# DA15.net
KiCad netlist of a schematic drawn in EasyEDA Pro
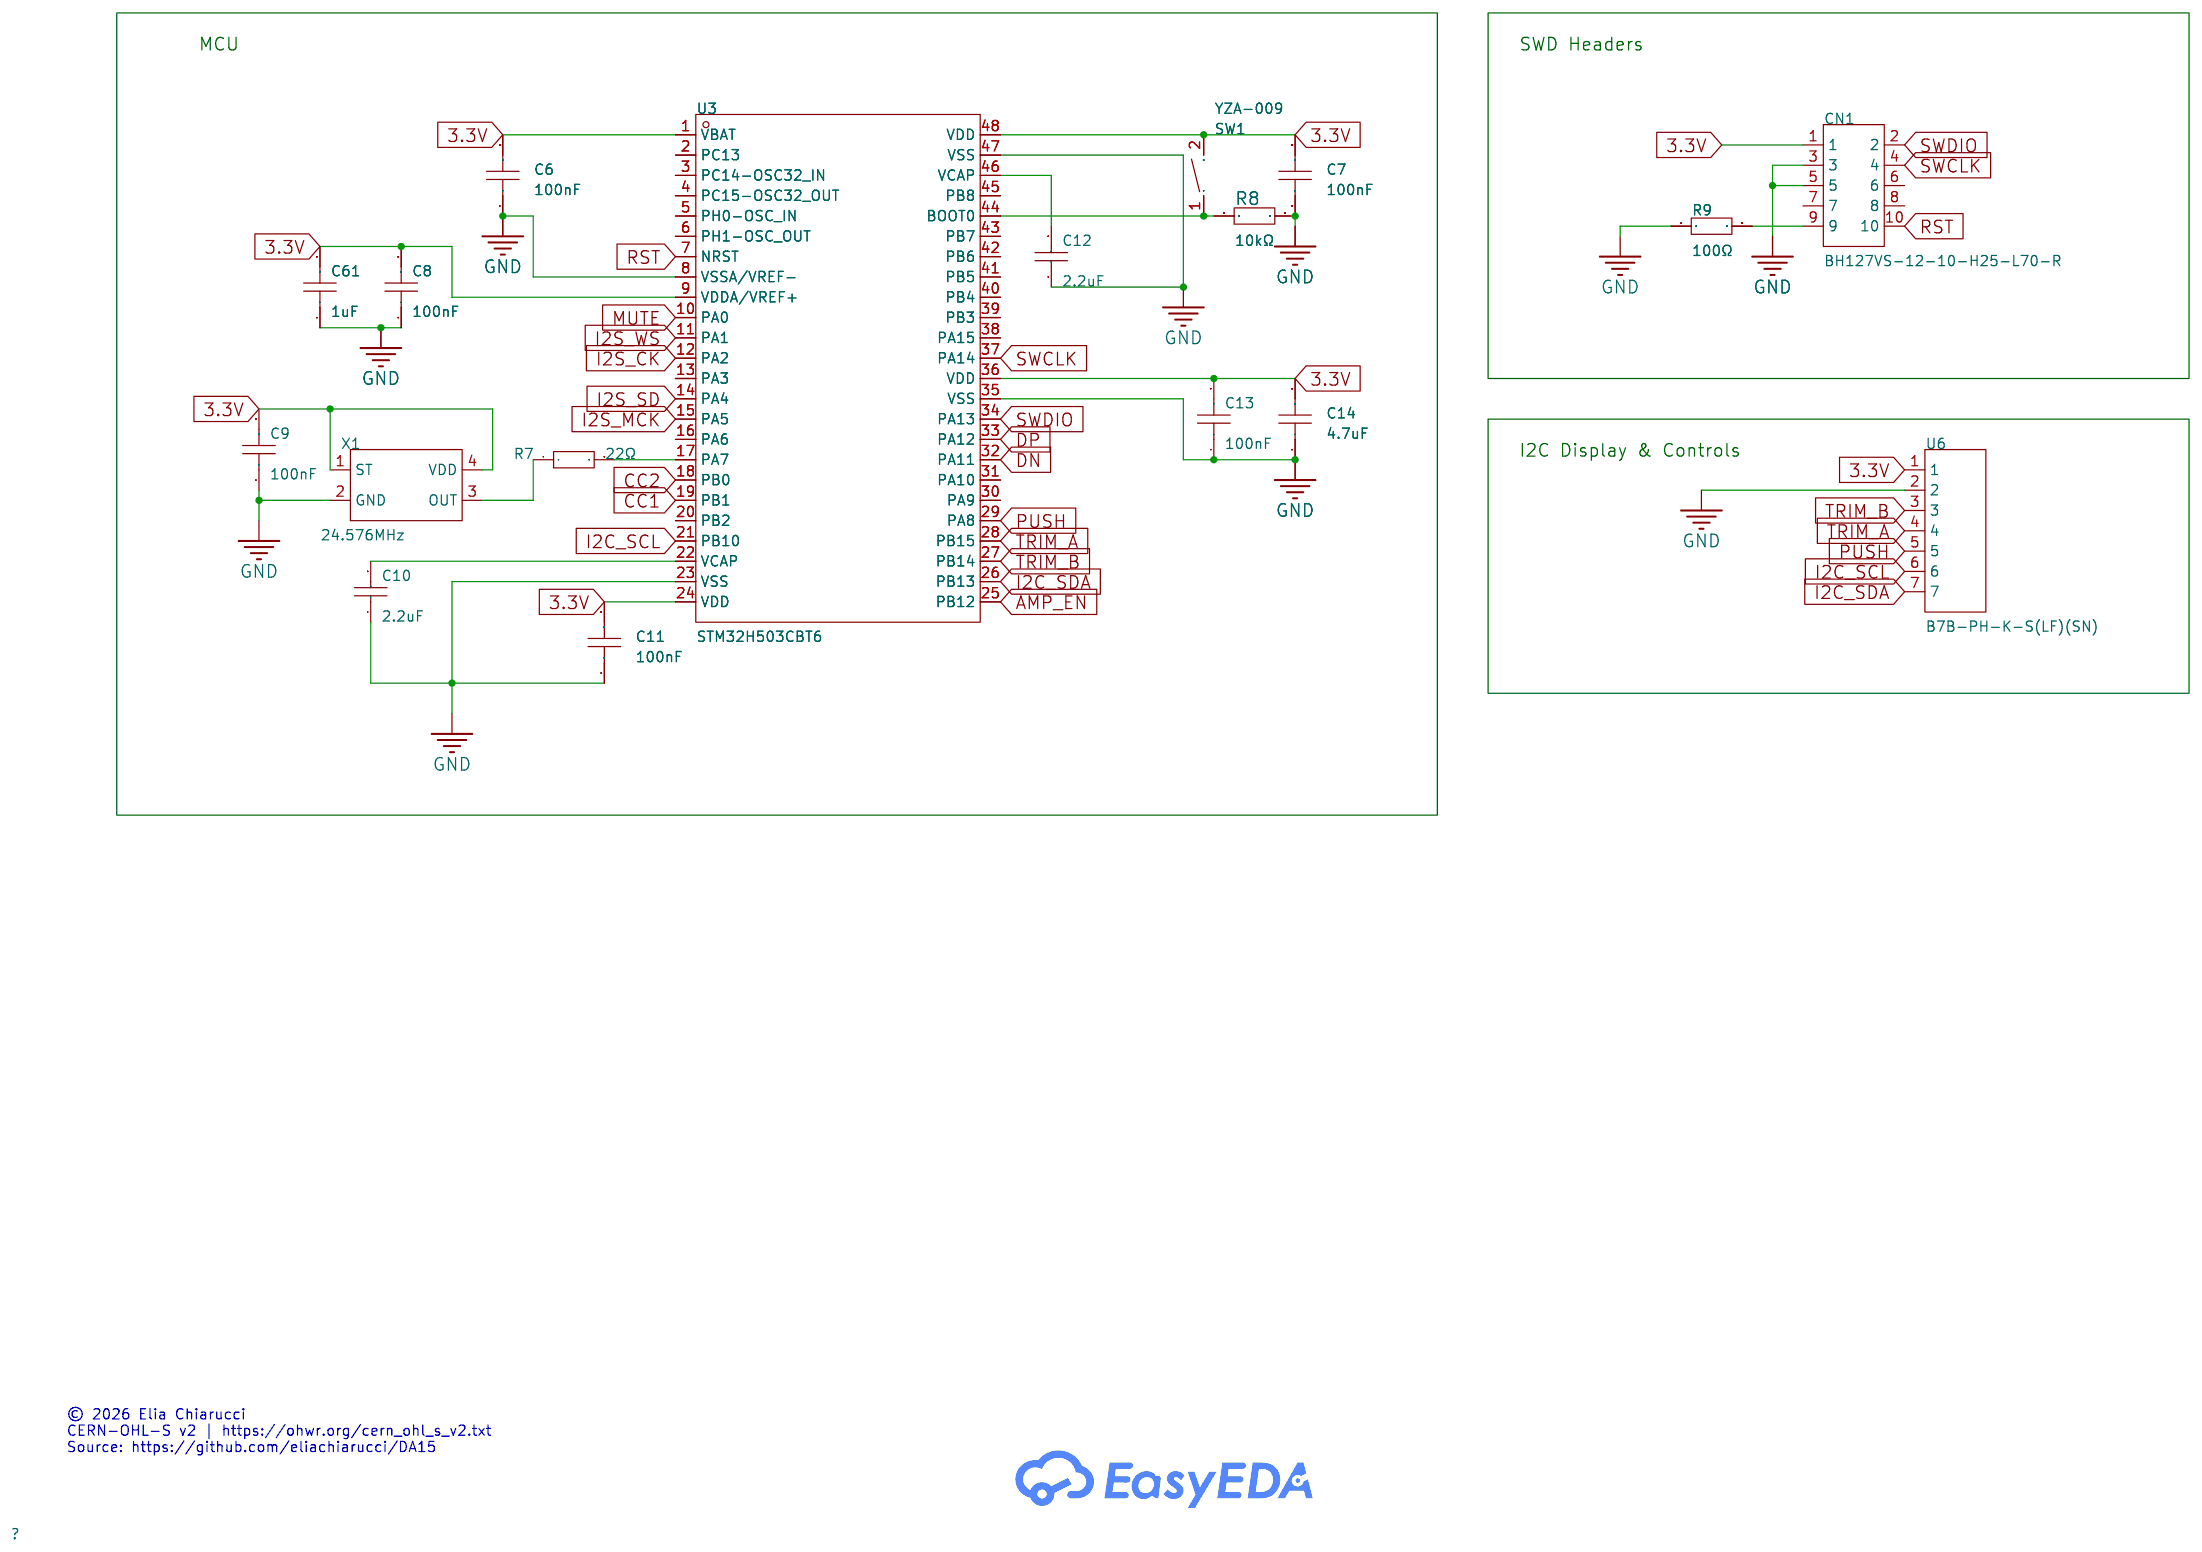
[diagram p0: Controller]
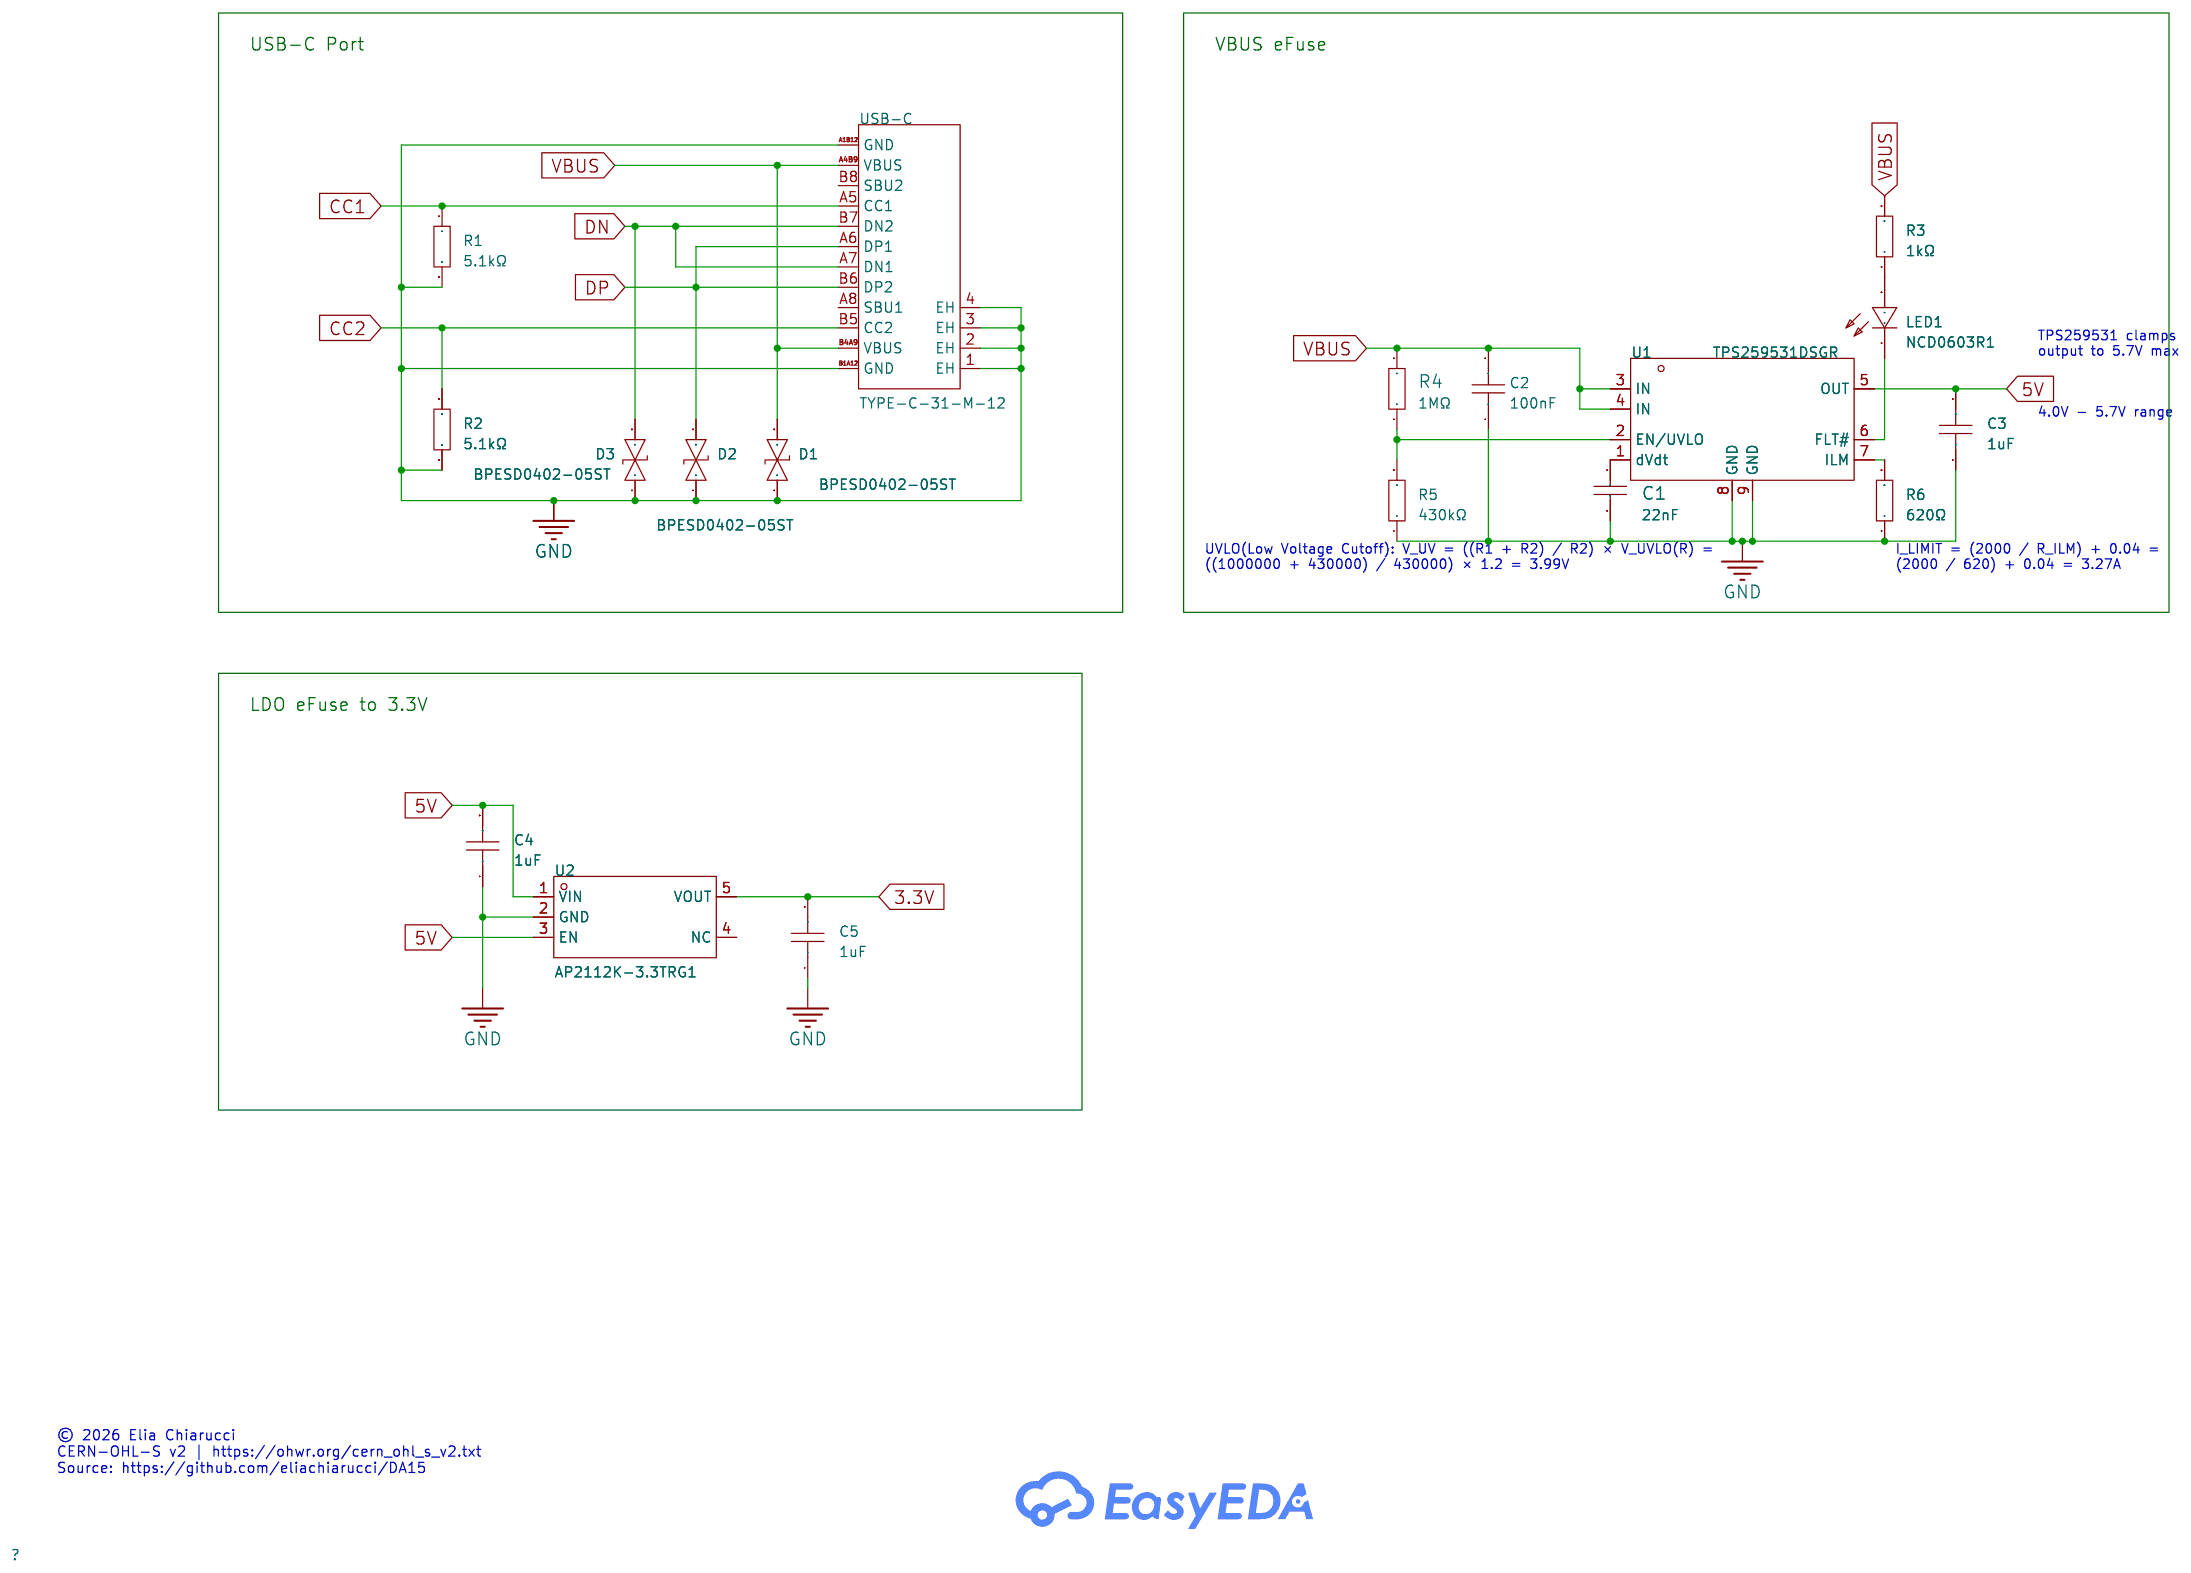
[diagram p1: Power]
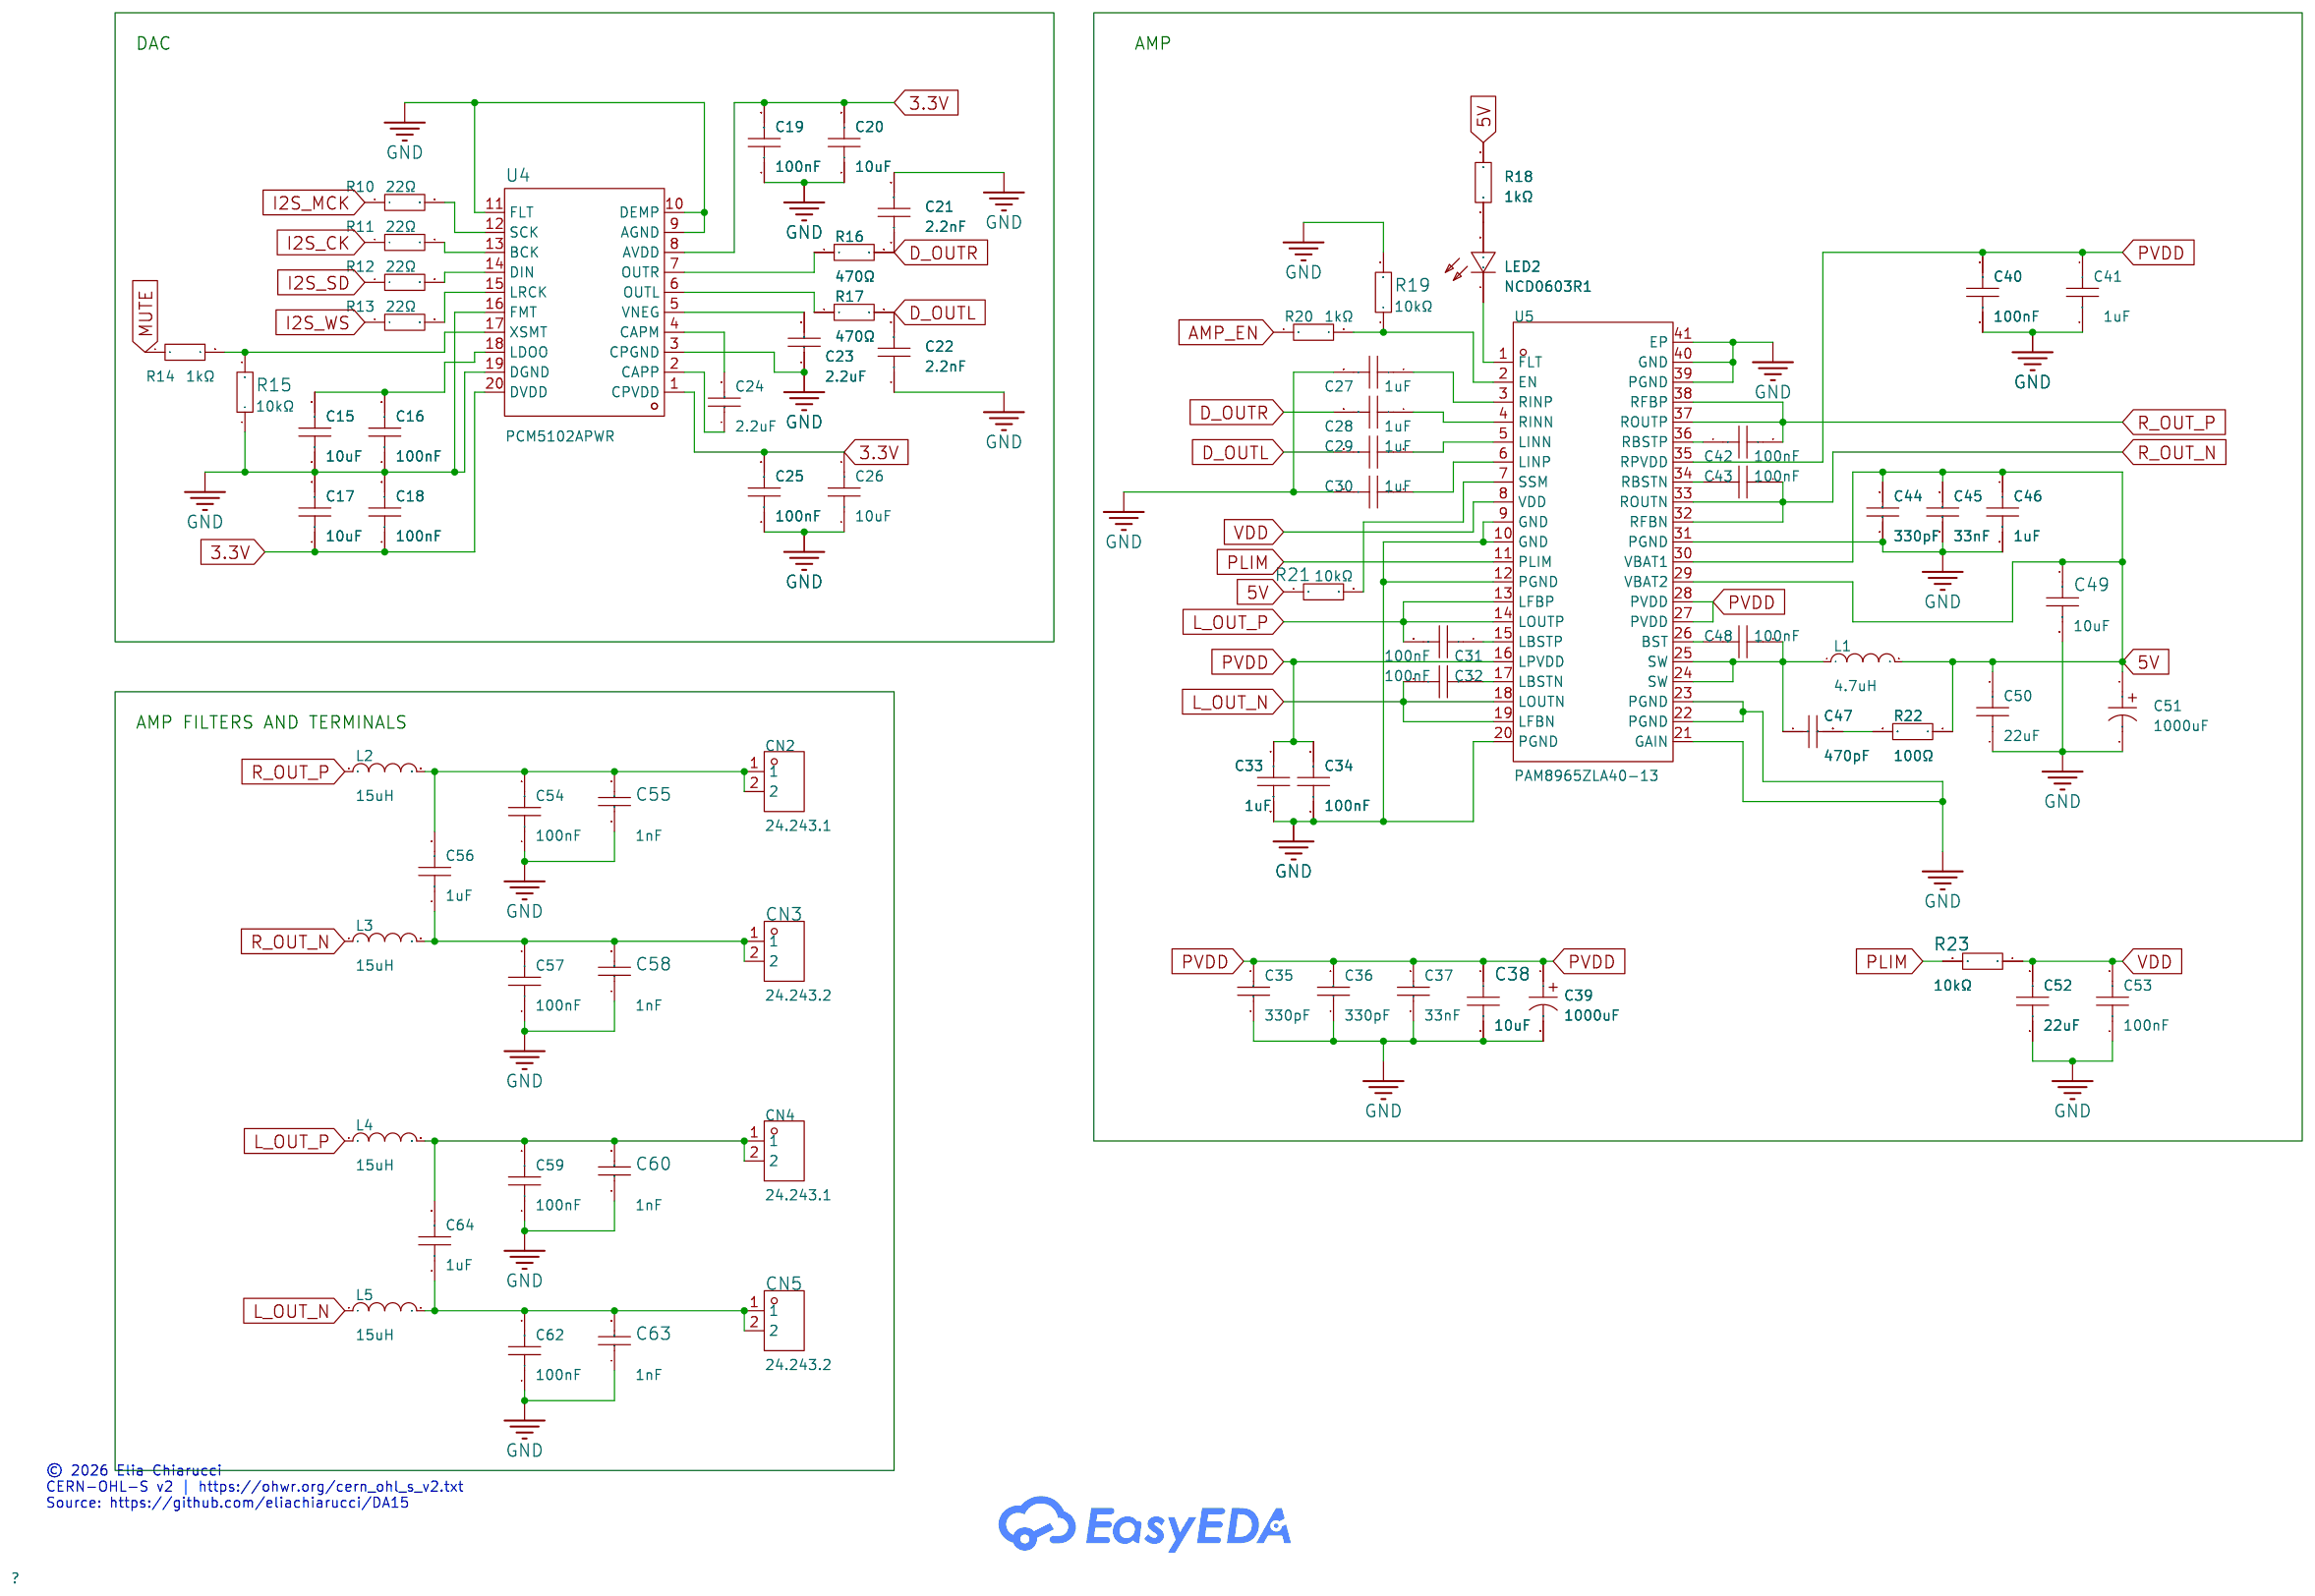
[diagram p2: Audio]

(export (version "E")
  (design (tool "Eeschema 10.0.6"))
  (components
    (comp (ref "C6")
      (value "100nF")
      (footprint "easyedapro:C0603")
      (description "Capacitance:100nF Tolerance:±10% Tolerance:±10% Voltage Rating:50V Temperature Coefficient:X7R")
      (fields
        (field (name "Manufacturer Part") "CC0603KRX7R9BB104")
        (field (name "Manufacturer") "YAGEO(国巨)")
      )
      (libsource (lib "easyedapro") (part "CC0603KRX7R9BB104"))
    )
    (comp (ref "C7")
      (value "100nF")
      (footprint "easyedapro:C0603")
      (description "Capacitance:100nF Tolerance:±10% Tolerance:±10% Voltage Rating:50V Temperature Coefficient:X7R")
      (fields
        (field (name "Manufacturer Part") "CC0603KRX7R9BB104")
        (field (name "Manufacturer") "YAGEO(国巨)")
      )
      (libsource (lib "easyedapro") (part "CC0603KRX7R9BB104"))
    )
    (comp (ref "C8")
      (value "100nF")
      (footprint "easyedapro:C0603")
      (description "Capacitance:100nF Tolerance:±10% Tolerance:±10% Voltage Rating:50V Temperature Coefficient:X7R")
      (fields
        (field (name "Manufacturer Part") "CC0603KRX7R9BB104")
        (field (name "Manufacturer") "YAGEO(国巨)")
      )
      (libsource (lib "easyedapro") (part "CC0603KRX7R9BB104"))
    )
    (comp (ref "C9")
      (value "100nF")
      (footprint "easyedapro:C0603")
      (description "Capacitance:100nF Tolerance:±10% Tolerance:±10% Voltage Rating:50V Temperature Coefficient:X7R")
      (fields
        (field (name "Manufacturer Part") "CC0603KRX7R9BB104")
        (field (name "Manufacturer") "YAGEO(国巨)")
      )
      (libsource (lib "easyedapro") (part "CC0603KRX7R9BB104"))
    )
    (comp (ref "C10")
      (value "2.2uF")
      (footprint "easyedapro:C0603")
      (description "Capacitance:2.2uF Tolerance:±10% Tolerance:±10% Voltage Rating:16V Temperature Coefficient:X5R")
      (fields
        (field (name "Manufacturer Part") "CL10A225KO8NNNC")
        (field (name "Manufacturer") "SAMSUNG(三星)")
      )
      (libsource (lib "easyedapro") (part "CL10A225KO8NNNC"))
    )
    (comp (ref "C11")
      (value "100nF")
      (footprint "easyedapro:C0603")
      (description "Capacitance:100nF Tolerance:±10% Tolerance:±10% Voltage Rating:50V Temperature Coefficient:X7R")
      (fields
        (field (name "Manufacturer Part") "CC0603KRX7R9BB104")
        (field (name "Manufacturer") "YAGEO(国巨)")
      )
      (libsource (lib "easyedapro") (part "CC0603KRX7R9BB104"))
    )
    (comp (ref "C12")
      (value "2.2uF")
      (footprint "easyedapro:C0603")
      (description "Capacitance:2.2uF Tolerance:±10% Tolerance:±10% Voltage Rating:16V Temperature Coefficient:X5R")
      (fields
        (field (name "Manufacturer Part") "CL10A225KO8NNNC")
        (field (name "Manufacturer") "SAMSUNG(三星)")
      )
      (libsource (lib "easyedapro") (part "CL10A225KO8NNNC"))
    )
    (comp (ref "C13")
      (value "100nF")
      (footprint "easyedapro:C0603")
      (description "Capacitance:100nF Tolerance:±10% Tolerance:±10% Voltage Rating:50V Temperature Coefficient:X7R")
      (fields
        (field (name "Manufacturer Part") "CC0603KRX7R9BB104")
        (field (name "Manufacturer") "YAGEO(国巨)")
      )
      (libsource (lib "easyedapro") (part "CC0603KRX7R9BB104"))
    )
    (comp (ref "C14")
      (value "4.7uF")
      (footprint "easyedapro:C0603")
      (description "Capacitance:4.7uF Tolerance:±10% Tolerance:±10% Voltage Rating:16V Temperature Coefficient:X5R")
      (fields
        (field (name "Manufacturer Part") "CL10A475KO8NNNC")
        (field (name "Manufacturer") "SAMSUNG(三星)")
      )
      (libsource (lib "easyedapro") (part "CL10A475KO8NNNC"))
    )
    (comp (ref "C61")
      (value "1uF")
      (footprint "easyedapro:C0603")
      (description "Capacitance:1uF Tolerance:±10% Tolerance:±10% Voltage Rating:50V Temperature Coefficient:X5R")
      (fields
        (field (name "Manufacturer Part") "CL10A105KB8NNNC")
        (field (name "Manufacturer") "SAMSUNG(三星)")
      )
      (libsource (lib "easyedapro") (part "CL10A105KB8NNNC"))
    )
    (comp (ref "CN1")
      (value "BH127VS-12-10-H25-L70-R")
      (footprint "easyedapro:CONN-SMD_10P-P1.27-V-M-R2-C5-LS5.8_BH127VS-12-10-H25-L70-R")
      (fields (field (name "Manufacturer") "XFCN(兴飞)"))
      (libsource (lib "easyedapro") (part "BH127VS-12-10-H25-L70-R"))
    )
    (comp (ref "R7")
      (value "22Ω")
      (footprint "easyedapro:R0603")
      (fields
        (field (name "Manufacturer Part") "0603WAF220JT5E")
        (field (name "Manufacturer") "UNI-ROYAL(厚声)")
      )
      (libsource (lib "easyedapro") (part "0603WAF220JT5E"))
    )
    (comp (ref "R8")
      (value "10kΩ")
      (footprint "easyedapro:R0603")
      (fields
        (field (name "Manufacturer Part") "0603WAF1002T5E")
        (field (name "Manufacturer") "UNI-ROYAL(厚声)")
      )
      (libsource (lib "easyedapro") (part "0603WAF1002T5E"))
    )
    (comp (ref "R9")
      (value "100Ω")
      (footprint "easyedapro:R0603")
      (fields
        (field (name "Manufacturer Part") "0603WAF1000T5E")
        (field (name "Manufacturer") "UNI-ROYAL(厚声)")
      )
      (libsource (lib "easyedapro") (part "0603WAF1000T5E"))
    )
    (comp (ref "SW1")
      (value "YZA-009")
      (footprint "easyedapro:SW-SMD_YZA-009")
      (fields (field (name "Manufacturer") "YIZHI(逸致)"))
      (libsource (lib "easyedapro") (part "YZA-009"))
    )
    (comp (ref "U3")
      (value "STM32H503CBT6")
      (footprint "easyedapro:LQFP-48_L7.0-W7.0-P0.50-LS9.0-BL")
      (fields (field (name "Manufacturer") "ST(意法半导体)"))
      (libsource (lib "easyedapro") (part "STM32H503CBT6"))
    )
    (comp (ref "U6")
      (value "B7B-PH-K-S(LF)(SN)")
      (footprint "easyedapro:CONN-TH_B7B-PH-K-S-LF-SN")
      (fields (field (name "Manufacturer") "JST"))
      (libsource (lib "easyedapro") (part "B7B-PH-K-S-(LF)(SN)"))
    )
    (comp (ref "X1")
      (value "24.576MHz")
      (footprint "easyedapro:OSC-SMD_4P-L2.5-W2.0-BL")
      (fields
        (field (name "Manufacturer Part") "OT3EL4C4JI-111OLP-24.576M")
        (field (name "Manufacturer") "YXC(扬兴晶振)")
      )
      (libsource (lib "easyedapro") (part "OT3EL4C4JI-111OLP-24.576M"))
    )
    (comp (ref "C1")
      (value "22nF")
      (footprint "easyedapro:C0603")
      (description "Capacitance:22nF Tolerance:±10% Tolerance:±10% Voltage Rating:50V Temperature Coefficient:X7R")
      (fields
        (field (name "Manufacturer Part") "CL10B223KB8NNNC")
        (field (name "Manufacturer") "SAMSUNG(三星)")
      )
      (libsource (lib "easyedapro") (part "CL10B223KB8NNNC"))
    )
    (comp (ref "C2")
      (value "100nF")
      (footprint "easyedapro:C0603")
      (description "Capacitance:100nF Tolerance:±10% Tolerance:±10% Voltage Rating:50V Temperature Coefficient:X7R")
      (fields
        (field (name "Manufacturer Part") "CC0603KRX7R9BB104")
        (field (name "Manufacturer") "YAGEO(国巨)")
      )
      (libsource (lib "easyedapro") (part "CC0603KRX7R9BB104"))
    )
    (comp (ref "C3")
      (value "1uF")
      (footprint "easyedapro:C0603")
      (description "Capacitance:1uF Tolerance:±10% Tolerance:±10% Voltage Rating:50V Temperature Coefficient:X5R")
      (fields
        (field (name "Manufacturer Part") "CL10A105KB8NNNC")
        (field (name "Manufacturer") "SAMSUNG(三星)")
      )
      (libsource (lib "easyedapro") (part "CL10A105KB8NNNC"))
    )
    (comp (ref "C4")
      (value "1uF")
      (footprint "easyedapro:C0603")
      (description "Capacitance:1uF Tolerance:±10% Tolerance:±10% Voltage Rating:50V Temperature Coefficient:X5R")
      (fields
        (field (name "Manufacturer Part") "CL10A105KB8NNNC")
        (field (name "Manufacturer") "SAMSUNG(三星)")
      )
      (libsource (lib "easyedapro") (part "CL10A105KB8NNNC"))
    )
    (comp (ref "C5")
      (value "1uF")
      (footprint "easyedapro:C0603")
      (description "Capacitance:1uF Tolerance:±10% Tolerance:±10% Voltage Rating:50V Temperature Coefficient:X5R")
      (fields
        (field (name "Manufacturer Part") "CL10A105KB8NNNC")
        (field (name "Manufacturer") "SAMSUNG(三星)")
      )
      (libsource (lib "easyedapro") (part "CL10A105KB8NNNC"))
    )
    (comp (ref "D1")
      (value "BPESD0402-05ST")
      (footprint "easyedapro:D0402-BI")
      (fields (field (name "Manufacturer") "BORN(伯恩半导体)"))
      (libsource (lib "easyedapro") (part "BPESD0402-05ST"))
    )
    (comp (ref "D2")
      (value "BPESD0402-05ST")
      (footprint "easyedapro:D0402-BI")
      (fields (field (name "Manufacturer") "BORN(伯恩半导体)"))
      (libsource (lib "easyedapro") (part "BPESD0402-05ST"))
    )
    (comp (ref "D3")
      (value "BPESD0402-05ST")
      (footprint "easyedapro:D0402-BI")
      (fields (field (name "Manufacturer") "BORN(伯恩半导体)"))
      (libsource (lib "easyedapro") (part "BPESD0402-05ST"))
    )
    (comp (ref "LED1")
      (value "NCD0603R1")
      (footprint "easyedapro:LED0603-RD_RED")
      (fields (field (name "Manufacturer") "国星光电"))
      (libsource (lib "easyedapro") (part "FC-DA1608HRK-620D"))
    )
    (comp (ref "R1")
      (value "5.1kΩ")
      (footprint "easyedapro:R0603")
      (fields
        (field (name "Manufacturer Part") "0603WAF5101T5E")
        (field (name "Manufacturer") "UNI-ROYAL(厚声)")
      )
      (libsource (lib "easyedapro") (part "0603WAF5101T5E"))
    )
    (comp (ref "R2")
      (value "5.1kΩ")
      (footprint "easyedapro:R0603")
      (fields
        (field (name "Manufacturer Part") "0603WAF5101T5E")
        (field (name "Manufacturer") "UNI-ROYAL(厚声)")
      )
      (libsource (lib "easyedapro") (part "0603WAF5101T5E"))
    )
    (comp (ref "R3")
      (value "1kΩ")
      (footprint "easyedapro:R0603")
      (fields
        (field (name "Manufacturer Part") "0603WAF1001T5E")
        (field (name "Manufacturer") "UNI-ROYAL(厚声)")
      )
      (libsource (lib "easyedapro") (part "0603WAF1001T5E"))
    )
    (comp (ref "R4")
      (value "1MΩ")
      (footprint "easyedapro:R0603")
      (fields
        (field (name "Manufacturer Part") "0603WAF1004T5E")
        (field (name "Manufacturer") "UNI-ROYAL(厚声)")
      )
      (libsource (lib "easyedapro") (part "0603WAF1004T5E"))
    )
    (comp (ref "R5")
      (value "430kΩ")
      (footprint "easyedapro:R0603")
      (fields
        (field (name "Manufacturer Part") "0603WAF4303T5E")
        (field (name "Manufacturer") "UNI-ROYAL(厚声)")
      )
      (libsource (lib "easyedapro") (part "0603WAF4303T5E"))
    )
    (comp (ref "R6")
      (value "620Ω")
      (footprint "easyedapro:R0603")
      (fields
        (field (name "Manufacturer Part") "0603WAF6200T5E")
        (field (name "Manufacturer") "UNI-ROYAL(厚声)")
      )
      (libsource (lib "easyedapro") (part "0603WAF6200T5E"))
    )
    (comp (ref "U1")
      (value "TPS259531DSGR")
      (footprint "easyedapro:WSON-8_L2.0-W2.0-P0.50-TL-EP")
      (fields (field (name "Manufacturer") "TI(德州仪器)"))
      (libsource (lib "easyedapro") (part "TPS259531DSGR"))
    )
    (comp (ref "U2")
      (value "AP2112K-3.3TRG1")
      (footprint "easyedapro:SOT-25-5_L2.9-W1.6-P0.95-LS2.8-BL")
      (fields (field (name "Manufacturer") "DIODES(美台)"))
      (libsource (lib "easyedapro") (part "AP2112K-3.3TRG1"))
    )
    (comp (ref "USB-C")
      (value "TYPE-C-31-M-12")
      (footprint "easyedapro:USB-C_SMD-TYPE-C-31-M-12_1")
      (fields (field (name "Manufacturer") "韩国韩荣"))
      (libsource (lib "easyedapro") (part "TYPE-C-31-M-12"))
    )
    (comp (ref "C15")
      (value "10uF")
      (footprint "easyedapro:C0603")
      (description "Capacitance:10uF Tolerance:±10% Tolerance:±10% Voltage Rating:10V Temperature Coefficient:X5R")
      (fields
        (field (name "Manufacturer Part") "CL10A106KP8NNNC")
        (field (name "Manufacturer") "SAMSUNG(三星)")
      )
      (libsource (lib "easyedapro") (part "CL10A106KP8NNNC"))
    )
    (comp (ref "C16")
      (value "100nF")
      (footprint "easyedapro:C0603")
      (description "Capacitance:100nF Tolerance:±10% Tolerance:±10% Voltage Rating:50V Temperature Coefficient:X7R")
      (fields
        (field (name "Manufacturer Part") "CC0603KRX7R9BB104")
        (field (name "Manufacturer") "YAGEO(国巨)")
      )
      (libsource (lib "easyedapro") (part "CC0603KRX7R9BB104"))
    )
    (comp (ref "C17")
      (value "10uF")
      (footprint "easyedapro:C0603")
      (description "Capacitance:10uF Tolerance:±10% Tolerance:±10% Voltage Rating:10V Temperature Coefficient:X5R")
      (fields
        (field (name "Manufacturer Part") "CL10A106KP8NNNC")
        (field (name "Manufacturer") "SAMSUNG(三星)")
      )
      (libsource (lib "easyedapro") (part "CL10A106KP8NNNC"))
    )
    (comp (ref "C18")
      (value "100nF")
      (footprint "easyedapro:C0603")
      (description "Capacitance:100nF Tolerance:±10% Tolerance:±10% Voltage Rating:50V Temperature Coefficient:X7R")
      (fields
        (field (name "Manufacturer Part") "CC0603KRX7R9BB104")
        (field (name "Manufacturer") "YAGEO(国巨)")
      )
      (libsource (lib "easyedapro") (part "CC0603KRX7R9BB104"))
    )
    (comp (ref "C19")
      (value "100nF")
      (footprint "easyedapro:C0603")
      (description "Capacitance:100nF Tolerance:±10% Tolerance:±10% Voltage Rating:50V Temperature Coefficient:X7R")
      (fields
        (field (name "Manufacturer Part") "CC0603KRX7R9BB104")
        (field (name "Manufacturer") "YAGEO(国巨)")
      )
      (libsource (lib "easyedapro") (part "CC0603KRX7R9BB104"))
    )
    (comp (ref "C20")
      (value "10uF")
      (footprint "easyedapro:C0603")
      (description "Capacitance:10uF Tolerance:±10% Tolerance:±10% Voltage Rating:10V Temperature Coefficient:X5R")
      (fields
        (field (name "Manufacturer Part") "CL10A106KP8NNNC")
        (field (name "Manufacturer") "SAMSUNG(三星)")
      )
      (libsource (lib "easyedapro") (part "CL10A106KP8NNNC"))
    )
    (comp (ref "C21")
      (value "2.2nF")
      (footprint "easyedapro:C0603")
      (fields
        (field (name "Manufacturer Part") "GCM1885C1H222FA16D")
        (field (name "Manufacturer") "muRata(村田)")
      )
      (libsource (lib "easyedapro") (part "GCM1885C1H222FA16D"))
    )
    (comp (ref "C22")
      (value "2.2nF")
      (footprint "easyedapro:C0603")
      (fields
        (field (name "Manufacturer Part") "GCM1885C1H222FA16D")
        (field (name "Manufacturer") "muRata(村田)")
      )
      (libsource (lib "easyedapro") (part "GCM1885C1H222FA16D"))
    )
    (comp (ref "C23")
      (value "2.2uF")
      (footprint "easyedapro:C0603")
      (description "Capacitance:2.2uF Tolerance:±10% Tolerance:±10% Voltage Rating:16V Temperature Coefficient:X5R")
      (fields
        (field (name "Manufacturer Part") "CL10A225KO8NNNC")
        (field (name "Manufacturer") "SAMSUNG(三星)")
      )
      (libsource (lib "easyedapro") (part "CL10A225KO8NNNC"))
    )
    (comp (ref "C24")
      (value "2.2uF")
      (footprint "easyedapro:C0603")
      (description "Capacitance:2.2uF Tolerance:±10% Tolerance:±10% Voltage Rating:16V Temperature Coefficient:X5R")
      (fields
        (field (name "Manufacturer Part") "CL10A225KO8NNNC")
        (field (name "Manufacturer") "SAMSUNG(三星)")
      )
      (libsource (lib "easyedapro") (part "CL10A225KO8NNNC"))
    )
    (comp (ref "C25")
      (value "100nF")
      (footprint "easyedapro:C0603")
      (description "Capacitance:100nF Tolerance:±10% Tolerance:±10% Voltage Rating:50V Temperature Coefficient:X7R")
      (fields
        (field (name "Manufacturer Part") "CC0603KRX7R9BB104")
        (field (name "Manufacturer") "YAGEO(国巨)")
      )
      (libsource (lib "easyedapro") (part "CC0603KRX7R9BB104"))
    )
    (comp (ref "C26")
      (value "10uF")
      (footprint "easyedapro:C0603")
      (description "Capacitance:10uF Tolerance:±10% Tolerance:±10% Voltage Rating:10V Temperature Coefficient:X5R")
      (fields
        (field (name "Manufacturer Part") "CL10A106KP8NNNC")
        (field (name "Manufacturer") "SAMSUNG(三星)")
      )
      (libsource (lib "easyedapro") (part "CL10A106KP8NNNC"))
    )
    (comp (ref "C27")
      (value "1uF")
      (footprint "easyedapro:C0603")
      (description "Capacitance:1uF Tolerance:±10% Tolerance:±10% Voltage Rating:50V Temperature Coefficient:X5R")
      (fields
        (field (name "Manufacturer Part") "CL10A105KB8NNNC")
        (field (name "Manufacturer") "SAMSUNG(三星)")
      )
      (libsource (lib "easyedapro") (part "CL10A105KB8NNNC"))
    )
    (comp (ref "C28")
      (value "1uF")
      (footprint "easyedapro:C0603")
      (description "Capacitance:1uF Tolerance:±10% Tolerance:±10% Voltage Rating:50V Temperature Coefficient:X5R")
      (fields
        (field (name "Manufacturer Part") "CL10A105KB8NNNC")
        (field (name "Manufacturer") "SAMSUNG(三星)")
      )
      (libsource (lib "easyedapro") (part "CL10A105KB8NNNC"))
    )
    (comp (ref "C29")
      (value "1uF")
      (footprint "easyedapro:C0603")
      (description "Capacitance:1uF Tolerance:±10% Tolerance:±10% Voltage Rating:50V Temperature Coefficient:X5R")
      (fields
        (field (name "Manufacturer Part") "CL10A105KB8NNNC")
        (field (name "Manufacturer") "SAMSUNG(三星)")
      )
      (libsource (lib "easyedapro") (part "CL10A105KB8NNNC"))
    )
    (comp (ref "C30")
      (value "1uF")
      (footprint "easyedapro:C0603")
      (description "Capacitance:1uF Tolerance:±10% Tolerance:±10% Voltage Rating:50V Temperature Coefficient:X5R")
      (fields
        (field (name "Manufacturer Part") "CL10A105KB8NNNC")
        (field (name "Manufacturer") "SAMSUNG(三星)")
      )
      (libsource (lib "easyedapro") (part "CL10A105KB8NNNC"))
    )
    (comp (ref "C31")
      (value "100nF")
      (footprint "easyedapro:C0603")
      (description "Capacitance:100nF Tolerance:±10% Tolerance:±10% Voltage Rating:50V Temperature Coefficient:X7R")
      (fields
        (field (name "Manufacturer Part") "CC0603KRX7R9BB104")
        (field (name "Manufacturer") "YAGEO(国巨)")
      )
      (libsource (lib "easyedapro") (part "CC0603KRX7R9BB104"))
    )
    (comp (ref "C32")
      (value "100nF")
      (footprint "easyedapro:C0603")
      (description "Capacitance:100nF Tolerance:±10% Tolerance:±10% Voltage Rating:50V Temperature Coefficient:X7R")
      (fields
        (field (name "Manufacturer Part") "CC0603KRX7R9BB104")
        (field (name "Manufacturer") "YAGEO(国巨)")
      )
      (libsource (lib "easyedapro") (part "CC0603KRX7R9BB104"))
    )
    (comp (ref "C33")
      (value "1uF")
      (footprint "easyedapro:C0603")
      (description "Capacitance:1uF Tolerance:±10% Tolerance:±10% Voltage Rating:50V Temperature Coefficient:X5R")
      (fields
        (field (name "Manufacturer Part") "CL10A105KB8NNNC")
        (field (name "Manufacturer") "SAMSUNG(三星)")
      )
      (libsource (lib "easyedapro") (part "CL10A105KB8NNNC"))
    )
    (comp (ref "C34")
      (value "100nF")
      (footprint "easyedapro:C0603")
      (description "Capacitance:100nF Tolerance:±10% Tolerance:±10% Voltage Rating:50V Temperature Coefficient:X7R")
      (fields
        (field (name "Manufacturer Part") "CC0603KRX7R9BB104")
        (field (name "Manufacturer") "YAGEO(国巨)")
      )
      (libsource (lib "easyedapro") (part "CC0603KRX7R9BB104"))
    )
    (comp (ref "C35")
      (value "330pF")
      (footprint "easyedapro:C0603")
      (description "Capacitance:330pF Tolerance:±5% Tolerance:±5% Voltage Rating:50V Temperature Coefficient:C0G")
      (fields
        (field (name "Manufacturer Part") "CL10C331JB8NNNC")
        (field (name "Manufacturer") "SAMSUNG(三星)")
      )
      (libsource (lib "easyedapro") (part "CL10C331JB8NNNC"))
    )
    (comp (ref "C36")
      (value "330pF")
      (footprint "easyedapro:C0603")
      (description "Capacitance:330pF Tolerance:±5% Tolerance:±5% Voltage Rating:50V Temperature Coefficient:C0G")
      (fields
        (field (name "Manufacturer Part") "CL10C331JB8NNNC")
        (field (name "Manufacturer") "SAMSUNG(三星)")
      )
      (libsource (lib "easyedapro") (part "CL10C331JB8NNNC"))
    )
    (comp (ref "C37")
      (value "33nF")
      (footprint "easyedapro:C0603")
      (description "Capacitance:33nF Tolerance:±10% Tolerance:±10% Voltage Rating:50V Temperature Coefficient:X7R")
      (fields
        (field (name "Manufacturer Part") "CL10B333KB8NNNC")
        (field (name "Manufacturer") "SAMSUNG(三星)")
      )
      (libsource (lib "easyedapro") (part "CL10B333KB8NNNC"))
    )
    (comp (ref "C38")
      (value "10uF")
      (footprint "easyedapro:C0603")
      (description "Capacitance:10uF Tolerance:±10% Tolerance:±10% Voltage Rating:25V Temperature Coefficient:X5R")
      (fields
        (field (name "Manufacturer Part") "GRM188R61E106KA73D")
        (field (name "Manufacturer") "muRata(村田)")
      )
      (libsource (lib "easyedapro") (part "GRM188R61E106KA73D"))
    )
    (comp (ref "C39")
      (value "1000uF")
      (footprint "easyedapro:CAP-TH_BD8.0-P3.50-D0.6-FD")
      (fields (field (name "Manufacturer Part") "PA25V1000M8X15") (field (name "Manufacturer") "JIERR(捷而瑞)"))
      (libsource (lib "easyedapro") (part "PA25V1000M8X15"))
    )
    (comp (ref "C40")
      (value "100nF")
      (footprint "easyedapro:C0603")
      (description "Capacitance:100nF Tolerance:±10% Tolerance:±10% Voltage Rating:50V Temperature Coefficient:X7R")
      (fields
        (field (name "Manufacturer Part") "CC0603KRX7R9BB104")
        (field (name "Manufacturer") "YAGEO(国巨)")
      )
      (libsource (lib "easyedapro") (part "CC0603KRX7R9BB104"))
    )
    (comp (ref "C41")
      (value "1uF")
      (footprint "easyedapro:C0603")
      (description "Capacitance:1uF Tolerance:±10% Tolerance:±10% Voltage Rating:50V Temperature Coefficient:X5R")
      (fields
        (field (name "Manufacturer Part") "CL10A105KB8NNNC")
        (field (name "Manufacturer") "SAMSUNG(三星)")
      )
      (libsource (lib "easyedapro") (part "CL10A105KB8NNNC"))
    )
    (comp (ref "C42")
      (value "100nF")
      (footprint "easyedapro:C0603")
      (description "Capacitance:100nF Tolerance:±10% Tolerance:±10% Voltage Rating:50V Temperature Coefficient:X7R")
      (fields
        (field (name "Manufacturer Part") "CC0603KRX7R9BB104")
        (field (name "Manufacturer") "YAGEO(国巨)")
      )
      (libsource (lib "easyedapro") (part "CC0603KRX7R9BB104"))
    )
    (comp (ref "C43")
      (value "100nF")
      (footprint "easyedapro:C0603")
      (description "Capacitance:100nF Tolerance:±10% Tolerance:±10% Voltage Rating:50V Temperature Coefficient:X7R")
      (fields
        (field (name "Manufacturer Part") "CC0603KRX7R9BB104")
        (field (name "Manufacturer") "YAGEO(国巨)")
      )
      (libsource (lib "easyedapro") (part "CC0603KRX7R9BB104"))
    )
    (comp (ref "C44")
      (value "330pF")
      (footprint "easyedapro:C0603")
      (description "Capacitance:330pF Tolerance:±5% Tolerance:±5% Voltage Rating:50V Temperature Coefficient:C0G")
      (fields
        (field (name "Manufacturer Part") "CL10C331JB8NNNC")
        (field (name "Manufacturer") "SAMSUNG(三星)")
      )
      (libsource (lib "easyedapro") (part "CL10C331JB8NNNC"))
    )
    (comp (ref "C45")
      (value "33nF")
      (footprint "easyedapro:C0603")
      (description "Capacitance:33nF Tolerance:±10% Tolerance:±10% Voltage Rating:50V Temperature Coefficient:X7R")
      (fields
        (field (name "Manufacturer Part") "CL10B333KB8NNNC")
        (field (name "Manufacturer") "SAMSUNG(三星)")
      )
      (libsource (lib "easyedapro") (part "CL10B333KB8NNNC"))
    )
    (comp (ref "C46")
      (value "1uF")
      (footprint "easyedapro:C0603")
      (description "Capacitance:1uF Tolerance:±10% Tolerance:±10% Voltage Rating:50V Temperature Coefficient:X5R")
      (fields
        (field (name "Manufacturer Part") "CL10A105KB8NNNC")
        (field (name "Manufacturer") "SAMSUNG(三星)")
      )
      (libsource (lib "easyedapro") (part "CL10A105KB8NNNC"))
    )
    (comp (ref "C47")
      (value "470pF")
      (footprint "easyedapro:C0603")
      (description "Capacitance:470pF Tolerance:±10% Tolerance:±10% Voltage Rating:50V Temperature Coefficient:X7R")
      (fields (field (name "Manufacturer Part") "0603B471K500NT") (field (name "Manufacturer") "FH(风华)"))
      (libsource (lib "easyedapro") (part "0603B471K500NT"))
    )
    (comp (ref "C48")
      (value "100nF")
      (footprint "easyedapro:C0603")
      (description "Capacitance:100nF Tolerance:±10% Tolerance:±10% Voltage Rating:50V Temperature Coefficient:X7R")
      (fields
        (field (name "Manufacturer Part") "CC0603KRX7R9BB104")
        (field (name "Manufacturer") "YAGEO(国巨)")
      )
      (libsource (lib "easyedapro") (part "CC0603KRX7R9BB104"))
    )
    (comp (ref "C49")
      (value "10uF")
      (footprint "easyedapro:C0603")
      (description "Capacitance:10uF Tolerance:±10% Tolerance:±10% Voltage Rating:25V Temperature Coefficient:X5R")
      (fields
        (field (name "Manufacturer Part") "GRM188R61E106KA73D")
        (field (name "Manufacturer") "muRata(村田)")
      )
      (libsource (lib "easyedapro") (part "GRM188R61E106KA73D"))
    )
    (comp (ref "C50")
      (value "22uF")
      (footprint "easyedapro:C0603")
      (description "Capacitance:22uF Tolerance:±20% Tolerance:±20% Voltage Rating:25V")
      (fields
        (field (name "Manufacturer Part") "GRM188C61E226ME01D")
        (field (name "Manufacturer") "muRata(村田)")
      )
      (libsource (lib "easyedapro") (part "GRM188C61E226ME01D"))
    )
    (comp (ref "C51")
      (value "1000uF")
      (footprint "easyedapro:CAP-TH_BD8.0-P3.50-D0.6-FD")
      (fields (field (name "Manufacturer Part") "PA25V1000M8X15") (field (name "Manufacturer") "JIERR(捷而瑞)"))
      (libsource (lib "easyedapro") (part "PA25V1000M8X15"))
    )
    (comp (ref "C52")
      (value "22uF")
      (footprint "easyedapro:C0603")
      (description "Capacitance:22uF Tolerance:±20% Tolerance:±20% Voltage Rating:25V")
      (fields
        (field (name "Manufacturer Part") "GRM188C61E226ME01D")
        (field (name "Manufacturer") "muRata(村田)")
      )
      (libsource (lib "easyedapro") (part "GRM188C61E226ME01D"))
    )
    (comp (ref "C53")
      (value "100nF")
      (footprint "easyedapro:C0603")
      (description "Capacitance:100nF Tolerance:±10% Tolerance:±10% Voltage Rating:50V Temperature Coefficient:X7R")
      (fields
        (field (name "Manufacturer Part") "CC0603KRX7R9BB104")
        (field (name "Manufacturer") "YAGEO(国巨)")
      )
      (libsource (lib "easyedapro") (part "CC0603KRX7R9BB104"))
    )
    (comp (ref "C54")
      (value "100nF")
      (footprint "easyedapro:C0603")
      (description "Capacitance:100nF Tolerance:±10% Tolerance:±10% Voltage Rating:50V Temperature Coefficient:X7R")
      (fields
        (field (name "Manufacturer Part") "CC0603KRX7R9BB104")
        (field (name "Manufacturer") "YAGEO(国巨)")
      )
      (libsource (lib "easyedapro") (part "CC0603KRX7R9BB104"))
    )
    (comp (ref "C55")
      (value "1nF")
      (footprint "easyedapro:C0603")
      (description "Capacitance:1nF Tolerance:±10% Tolerance:±10% Voltage Rating:50V Temperature Coefficient:X7R")
      (fields
        (field (name "Manufacturer Part") "CL10B102KB8NNNC")
        (field (name "Manufacturer") "SAMSUNG(三星)")
      )
      (libsource (lib "easyedapro") (part "CL10B102KB8NNNC"))
    )
    (comp (ref "C56")
      (value "1uF")
      (footprint "easyedapro:C0603")
      (description "Capacitance:1uF Tolerance:±10% Tolerance:±10% Voltage Rating:50V Temperature Coefficient:X5R")
      (fields
        (field (name "Manufacturer Part") "CL10A105KB8NNNC")
        (field (name "Manufacturer") "SAMSUNG(三星)")
      )
      (libsource (lib "easyedapro") (part "CL10A105KB8NNNC"))
    )
    (comp (ref "C57")
      (value "100nF")
      (footprint "easyedapro:C0603")
      (description "Capacitance:100nF Tolerance:±10% Tolerance:±10% Voltage Rating:50V Temperature Coefficient:X7R")
      (fields
        (field (name "Manufacturer Part") "CC0603KRX7R9BB104")
        (field (name "Manufacturer") "YAGEO(国巨)")
      )
      (libsource (lib "easyedapro") (part "CC0603KRX7R9BB104"))
    )
    (comp (ref "C58")
      (value "1nF")
      (footprint "easyedapro:C0603")
      (description "Capacitance:1nF Tolerance:±10% Tolerance:±10% Voltage Rating:50V Temperature Coefficient:X7R")
      (fields
        (field (name "Manufacturer Part") "CL10B102KB8NNNC")
        (field (name "Manufacturer") "SAMSUNG(三星)")
      )
      (libsource (lib "easyedapro") (part "CL10B102KB8NNNC"))
    )
    (comp (ref "C59")
      (value "100nF")
      (footprint "easyedapro:C0603")
      (description "Capacitance:100nF Tolerance:±10% Tolerance:±10% Voltage Rating:50V Temperature Coefficient:X7R")
      (fields
        (field (name "Manufacturer Part") "CC0603KRX7R9BB104")
        (field (name "Manufacturer") "YAGEO(国巨)")
      )
      (libsource (lib "easyedapro") (part "CC0603KRX7R9BB104"))
    )
    (comp (ref "C60")
      (value "1nF")
      (footprint "easyedapro:C0603")
      (description "Capacitance:1nF Tolerance:±10% Tolerance:±10% Voltage Rating:50V Temperature Coefficient:X7R")
      (fields
        (field (name "Manufacturer Part") "CL10B102KB8NNNC")
        (field (name "Manufacturer") "SAMSUNG(三星)")
      )
      (libsource (lib "easyedapro") (part "CL10B102KB8NNNC"))
    )
    (comp (ref "C62")
      (value "100nF")
      (footprint "easyedapro:C0603")
      (description "Capacitance:100nF Tolerance:±10% Tolerance:±10% Voltage Rating:50V Temperature Coefficient:X7R")
      (fields
        (field (name "Manufacturer Part") "CC0603KRX7R9BB104")
        (field (name "Manufacturer") "YAGEO(国巨)")
      )
      (libsource (lib "easyedapro") (part "CC0603KRX7R9BB104"))
    )
    (comp (ref "C63")
      (value "1nF")
      (footprint "easyedapro:C0603")
      (description "Capacitance:1nF Tolerance:±10% Tolerance:±10% Voltage Rating:50V Temperature Coefficient:X7R")
      (fields
        (field (name "Manufacturer Part") "CL10B102KB8NNNC")
        (field (name "Manufacturer") "SAMSUNG(三星)")
      )
      (libsource (lib "easyedapro") (part "CL10B102KB8NNNC"))
    )
    (comp (ref "C64")
      (value "1uF")
      (footprint "easyedapro:C0603")
      (description "Capacitance:1uF Tolerance:±10% Tolerance:±10% Voltage Rating:50V Temperature Coefficient:X5R")
      (fields
        (field (name "Manufacturer Part") "CL10A105KB8NNNC")
        (field (name "Manufacturer") "SAMSUNG(三星)")
      )
      (libsource (lib "easyedapro") (part "CL10A105KB8NNNC"))
    )
    (comp (ref "CN2")
      (value "24.243.1")
      (footprint "easyedapro:CONN-TH_24.243.1_RED")
      (description "Connector Type:Terminal Voltage Rating:60V Current Rating:24A")
      (fields (field (name "Manufacturer") "AMASS(艾迈斯)"))
      (libsource (lib "easyedapro") (part "24.243.1"))
    )
    (comp (ref "CN3")
      (value "24.243.2")
      (footprint "easyedapro:CONN-TH_24.243.2")
      (description "Connector Type:Terminal Voltage Rating:60V Current Rating:24A")
      (fields (field (name "Manufacturer") "AMASS(艾迈斯)"))
      (libsource (lib "easyedapro") (part "24.243.2"))
    )
    (comp (ref "CN4")
      (value "24.243.1")
      (footprint "easyedapro:CONN-TH_24.243.1_RED")
      (description "Connector Type:Terminal Voltage Rating:60V Current Rating:24A")
      (fields (field (name "Manufacturer") "AMASS(艾迈斯)"))
      (libsource (lib "easyedapro") (part "24.243.1"))
    )
    (comp (ref "CN5")
      (value "24.243.2")
      (footprint "easyedapro:CONN-TH_24.243.2")
      (description "Connector Type:Terminal Voltage Rating:60V Current Rating:24A")
      (fields (field (name "Manufacturer") "AMASS(艾迈斯)"))
      (libsource (lib "easyedapro") (part "24.243.2"))
    )
    (comp (ref "L1")
      (value "4.7uH")
      (footprint "easyedapro:IND-SMD_L7.3-W6.6_MHCI06030")
      (fields (field (name "Manufacturer Part") "SRP7028A-4R7M") (field (name "Manufacturer") "BOURNS"))
      (libsource (lib "easyedapro") (part "SRP7028A-4R7M"))
    )
    (comp (ref "L2")
      (value "15uH")
      (footprint "easyedapro:IND-SMD_L11.6-W10.1")
      (fields (field (name "Manufacturer Part") "CYA1040-15UH") (field (name "Manufacturer") "SHOU HAN(首韩)"))
      (libsource (lib "easyedapro") (part "CYA1040-15UH"))
    )
    (comp (ref "L3")
      (value "15uH")
      (footprint "easyedapro:IND-SMD_L11.6-W10.1")
      (fields (field (name "Manufacturer Part") "CYA1040-15UH") (field (name "Manufacturer") "SHOU HAN(首韩)"))
      (libsource (lib "easyedapro") (part "CYA1040-15UH"))
    )
    (comp (ref "L4")
      (value "15uH")
      (footprint "easyedapro:IND-SMD_L11.6-W10.1")
      (fields (field (name "Manufacturer Part") "CYA1040-15UH") (field (name "Manufacturer") "SHOU HAN(首韩)"))
      (libsource (lib "easyedapro") (part "CYA1040-15UH"))
    )
    (comp (ref "L5")
      (value "15uH")
      (footprint "easyedapro:IND-SMD_L11.6-W10.1")
      (fields (field (name "Manufacturer Part") "CYA1040-15UH") (field (name "Manufacturer") "SHOU HAN(首韩)"))
      (libsource (lib "easyedapro") (part "CYA1040-15UH"))
    )
    (comp (ref "LED2")
      (value "NCD0603R1")
      (footprint "easyedapro:LED0603-RD_RED")
      (fields (field (name "Manufacturer") "国星光电"))
      (libsource (lib "easyedapro") (part "FC-DA1608HRK-620D"))
    )
    (comp (ref "R10")
      (value "22Ω")
      (footprint "easyedapro:R0603")
      (fields
        (field (name "Manufacturer Part") "0603WAF220JT5E")
        (field (name "Manufacturer") "UNI-ROYAL(厚声)")
      )
      (libsource (lib "easyedapro") (part "0603WAF220JT5E"))
    )
    (comp (ref "R11")
      (value "22Ω")
      (footprint "easyedapro:R0603")
      (fields
        (field (name "Manufacturer Part") "0603WAF220JT5E")
        (field (name "Manufacturer") "UNI-ROYAL(厚声)")
      )
      (libsource (lib "easyedapro") (part "0603WAF220JT5E"))
    )
    (comp (ref "R12")
      (value "22Ω")
      (footprint "easyedapro:R0603")
      (fields
        (field (name "Manufacturer Part") "0603WAF220JT5E")
        (field (name "Manufacturer") "UNI-ROYAL(厚声)")
      )
      (libsource (lib "easyedapro") (part "0603WAF220JT5E"))
    )
    (comp (ref "R13")
      (value "22Ω")
      (footprint "easyedapro:R0603")
      (fields
        (field (name "Manufacturer Part") "0603WAF220JT5E")
        (field (name "Manufacturer") "UNI-ROYAL(厚声)")
      )
      (libsource (lib "easyedapro") (part "0603WAF220JT5E"))
    )
    (comp (ref "R14")
      (value "1kΩ")
      (footprint "easyedapro:R0603")
      (fields
        (field (name "Manufacturer Part") "0603WAF1001T5E")
        (field (name "Manufacturer") "UNI-ROYAL(厚声)")
      )
      (libsource (lib "easyedapro") (part "0603WAF1001T5E"))
    )
    (comp (ref "R15")
      (value "10kΩ")
      (footprint "easyedapro:R0603")
      (fields
        (field (name "Manufacturer Part") "0603WAF1002T5E")
        (field (name "Manufacturer") "UNI-ROYAL(厚声)")
      )
      (libsource (lib "easyedapro") (part "0603WAF1002T5E"))
    )
    (comp (ref "R16")
      (value "470Ω")
      (footprint "easyedapro:R0603")
      (fields
        (field (name "Manufacturer Part") "0603WAF4700T5E")
        (field (name "Manufacturer") "UNI-ROYAL(厚声)")
      )
      (libsource (lib "easyedapro") (part "0603WAF4700T5E"))
    )
    (comp (ref "R17")
      (value "470Ω")
      (footprint "easyedapro:R0603")
      (fields
        (field (name "Manufacturer Part") "0603WAF4700T5E")
        (field (name "Manufacturer") "UNI-ROYAL(厚声)")
      )
      (libsource (lib "easyedapro") (part "0603WAF4700T5E"))
    )
    (comp (ref "R18")
      (value "1kΩ")
      (footprint "easyedapro:R0603")
      (fields
        (field (name "Manufacturer Part") "0603WAF1001T5E")
        (field (name "Manufacturer") "UNI-ROYAL(厚声)")
      )
      (libsource (lib "easyedapro") (part "0603WAF1001T5E"))
    )
    (comp (ref "R19")
      (value "10kΩ")
      (footprint "easyedapro:R0603")
      (fields
        (field (name "Manufacturer Part") "0603WAF1002T5E")
        (field (name "Manufacturer") "UNI-ROYAL(厚声)")
      )
      (libsource (lib "easyedapro") (part "0603WAF1002T5E"))
    )
    (comp (ref "R20")
      (value "1kΩ")
      (footprint "easyedapro:R0603")
      (fields
        (field (name "Manufacturer Part") "0603WAF1001T5E")
        (field (name "Manufacturer") "UNI-ROYAL(厚声)")
      )
      (libsource (lib "easyedapro") (part "0603WAF1001T5E"))
    )
    (comp (ref "R21")
      (value "10kΩ")
      (footprint "easyedapro:R0603")
      (fields
        (field (name "Manufacturer Part") "0603WAF1002T5E")
        (field (name "Manufacturer") "UNI-ROYAL(厚声)")
      )
      (libsource (lib "easyedapro") (part "0603WAF1002T5E"))
    )
    (comp (ref "R22")
      (value "100Ω")
      (footprint "easyedapro:R0603")
      (fields
        (field (name "Manufacturer Part") "0603WAF1000T5E")
        (field (name "Manufacturer") "UNI-ROYAL(厚声)")
      )
      (libsource (lib "easyedapro") (part "0603WAF1000T5E"))
    )
    (comp (ref "R23")
      (value "10kΩ")
      (footprint "easyedapro:R0603")
      (fields
        (field (name "Manufacturer Part") "0603WAF1002T5E")
        (field (name "Manufacturer") "UNI-ROYAL(厚声)")
      )
      (libsource (lib "easyedapro") (part "0603WAF1002T5E"))
    )
    (comp (ref "U4")
      (value "PCM5102APWR")
      (footprint "easyedapro:TSSOP-20_L6.5-W4.4-P0.65-LS6.4-BL")
      (fields (field (name "Manufacturer") "TI(德州仪器)"))
      (libsource (lib "easyedapro") (part "PCM5102APWR"))
    )
    (comp (ref "U5")
      (value "PAM8965ZLA40-13")
      (footprint "easyedapro:WQFN-40_L5.0-W5.0-P0.40-TL-EP3.5")
      (fields (field (name "Manufacturer") "DIODES(美台)"))
      (libsource (lib "easyedapro") (part "PAM8965ZLA40-13"))
    )
  )
  (nets
    (net (code "1") (name "3.3V") (class "Default")
      (node (ref "C11") (pin "2") (pinfunction "2_2") (pintype "unspecified"))
      (node (ref "C13") (pin "2") (pinfunction "2_2") (pintype "unspecified"))
      (node (ref "C14") (pin "2") (pinfunction "2_2") (pintype "unspecified"))
      (node (ref "C17") (pin "1") (pinfunction "1_1") (pintype "unspecified"))
      (node (ref "C18") (pin "1") (pinfunction "1_1") (pintype "unspecified"))
      (node (ref "C19") (pin "2") (pinfunction "2_2") (pintype "unspecified"))
      (node (ref "C20") (pin "2") (pinfunction "2_2") (pintype "unspecified"))
      (node (ref "C25") (pin "2") (pinfunction "2_2") (pintype "unspecified"))
      (node (ref "C26") (pin "2") (pinfunction "2_2") (pintype "unspecified"))
      (node (ref "C5") (pin "2") (pinfunction "2_2") (pintype "unspecified"))
      (node (ref "C6") (pin "2") (pinfunction "2_2") (pintype "unspecified"))
      (node (ref "C61") (pin "2") (pinfunction "2_2") (pintype "unspecified"))
      (node (ref "C7") (pin "2") (pinfunction "2_2") (pintype "unspecified"))
      (node (ref "C8") (pin "2") (pinfunction "2_2") (pintype "unspecified"))
      (node (ref "C9") (pin "2") (pinfunction "2_2") (pintype "unspecified"))
      (node (ref "CN1") (pin "1") (pinfunction "1_1") (pintype "unspecified"))
      (node (ref "SW1") (pin "2") (pinfunction "2_2") (pintype "unspecified"))
      (node (ref "U2") (pin "5") (pinfunction "VOUT_5") (pintype "unspecified"))
      (node (ref "U3") (pin "1") (pinfunction "VBAT_1") (pintype "unspecified"))
      (node (ref "U3") (pin "24") (pinfunction "VDD_24") (pintype "unspecified"))
      (node (ref "U3") (pin "36") (pinfunction "VDD_36") (pintype "unspecified"))
      (node (ref "U3") (pin "48") (pinfunction "VDD_48") (pintype "unspecified"))
      (node (ref "U3") (pin "9") (pinfunction "VDDA/VREF+_9") (pintype "unspecified"))
      (node (ref "U4") (pin "1") (pinfunction "CPVDD_1") (pintype "input"))
      (node (ref "U4") (pin "20") (pinfunction "DVDD_20") (pintype "input"))
      (node (ref "U4") (pin "8") (pinfunction "AVDD_8") (pintype "input"))
      (node (ref "U6") (pin "1") (pinfunction "1_1") (pintype "unspecified"))
      (node (ref "X1") (pin "1") (pinfunction "ST_1") (pintype "unspecified"))
      (node (ref "X1") (pin "4") (pinfunction "VDD_4") (pintype "unspecified"))
    )
    (net (code "2") (name "5V") (class "Default")
      (node (ref "C3") (pin "2") (pinfunction "2_2") (pintype "unspecified"))
      (node (ref "C4") (pin "2") (pinfunction "2_2") (pintype "unspecified"))
      (node (ref "C44") (pin "2") (pinfunction "2_2") (pintype "input"))
      (node (ref "C45") (pin "2") (pinfunction "2_2") (pintype "input"))
      (node (ref "C46") (pin "1") (pinfunction "1_1") (pintype "unspecified"))
      (node (ref "C49") (pin "1") (pinfunction "1_1") (pintype "input"))
      (node (ref "C50") (pin "2") (pinfunction "2_2") (pintype "unspecified"))
      (node (ref "C51") (pin "1") (pinfunction "1_1") (pintype "input"))
      (node (ref "L1") (pin "2") (pinfunction "2_2") (pintype "unspecified"))
      (node (ref "R18") (pin "2") (pinfunction "2_2") (pintype "input"))
      (node (ref "R21") (pin "1") (pinfunction "1_1") (pintype "input"))
      (node (ref "R22") (pin "1") (pinfunction "1_1") (pintype "input"))
      (node (ref "U1") (pin "5") (pinfunction "OUT_5") (pintype "unspecified"))
      (node (ref "U2") (pin "1") (pinfunction "VIN_1") (pintype "unspecified"))
      (node (ref "U2") (pin "3") (pinfunction "EN_3") (pintype "unspecified"))
      (node (ref "U5") (pin "29") (pinfunction "VBAT2_29") (pintype "unspecified"))
      (node (ref "U5") (pin "30") (pinfunction "VBAT1_30") (pintype "unspecified"))
    )
    (net (code "3") (name "AMP_EN") (class "Default")
      (node (ref "R20") (pin "1") (pinfunction "1_1") (pintype "input"))
      (node (ref "U3") (pin "25") (pinfunction "PB12_25") (pintype "unspecified"))
    )
    (net (code "4") (name "CC1") (class "Default")
      (node (ref "R1") (pin "1") (pinfunction "1_1") (pintype "input"))
      (node (ref "U3") (pin "19") (pinfunction "PB1_19") (pintype "unspecified"))
      (node (ref "USB-C") (pin "A5") (pinfunction "CC1_A5") (pintype "unspecified"))
    )
    (net (code "5") (name "CC2") (class "Default")
      (node (ref "R2") (pin "1") (pinfunction "1_1") (pintype "input"))
      (node (ref "U3") (pin "18") (pinfunction "PB0_18") (pintype "unspecified"))
      (node (ref "USB-C") (pin "B5") (pinfunction "CC2_B5") (pintype "unspecified"))
    )
    (net (code "6") (name "DN") (class "Default")
      (node (ref "D3") (pin "2") (pinfunction "2_2") (pintype "unspecified"))
      (node (ref "U3") (pin "32") (pinfunction "PA11_32") (pintype "unspecified"))
      (node (ref "USB-C") (pin "A7") (pinfunction "DN1_A7") (pintype "unspecified"))
      (node (ref "USB-C") (pin "B7") (pinfunction "DN2_B7") (pintype "unspecified"))
    )
    (net (code "7") (name "DP") (class "Default")
      (node (ref "D2") (pin "2") (pinfunction "2_2") (pintype "unspecified"))
      (node (ref "U3") (pin "33") (pinfunction "PA12_33") (pintype "unspecified"))
      (node (ref "USB-C") (pin "A6") (pinfunction "DP1_A6") (pintype "unspecified"))
      (node (ref "USB-C") (pin "B6") (pinfunction "DP2_B6") (pintype "unspecified"))
    )
    (net (code "8") (name "D_OUTL") (class "Default")
      (node (ref "C22") (pin "2") (pinfunction "2_2") (pintype "unspecified"))
      (node (ref "C29") (pin "2") (pinfunction "2_2") (pintype "unspecified"))
      (node (ref "R17") (pin "2") (pinfunction "2_2") (pintype "input"))
    )
    (net (code "9") (name "D_OUTR") (class "Default")
      (node (ref "C21") (pin "1") (pinfunction "1_1") (pintype "unspecified"))
      (node (ref "C28") (pin "2") (pinfunction "2_2") (pintype "unspecified"))
      (node (ref "R16") (pin "2") (pinfunction "2_2") (pintype "input"))
    )
    (net (code "10") (name "GND") (class "Default")
      (node (ref "C1") (pin "2") (pinfunction "2_2") (pintype "input"))
      (node (ref "C10") (pin "1") (pinfunction "1_1") (pintype "input"))
      (node (ref "C11") (pin "1") (pinfunction "1_1") (pintype "unspecified"))
      (node (ref "C12") (pin "1") (pinfunction "1_1") (pintype "input"))
      (node (ref "C13") (pin "1") (pinfunction "1_1") (pintype "unspecified"))
      (node (ref "C14") (pin "1") (pinfunction "1_1") (pintype "unspecified"))
      (node (ref "C15") (pin "1") (pinfunction "1_1") (pintype "unspecified"))
      (node (ref "C16") (pin "1") (pinfunction "1_1") (pintype "unspecified"))
      (node (ref "C17") (pin "2") (pinfunction "2_2") (pintype "unspecified"))
      (node (ref "C18") (pin "2") (pinfunction "2_2") (pintype "unspecified"))
      (node (ref "C19") (pin "1") (pinfunction "1_1") (pintype "unspecified"))
      (node (ref "C2") (pin "1") (pinfunction "1_1") (pintype "unspecified"))
      (node (ref "C20") (pin "1") (pinfunction "1_1") (pintype "unspecified"))
      (node (ref "C21") (pin "2") (pinfunction "2_2") (pintype "unspecified"))
      (node (ref "C22") (pin "1") (pinfunction "1_1") (pintype "unspecified"))
      (node (ref "C23") (pin "1") (pinfunction "1_1") (pintype "input"))
      (node (ref "C25") (pin "1") (pinfunction "1_1") (pintype "unspecified"))
      (node (ref "C26") (pin "1") (pinfunction "1_1") (pintype "unspecified"))
      (node (ref "C27") (pin "2") (pinfunction "2_2") (pintype "unspecified"))
      (node (ref "C3") (pin "1") (pinfunction "1_1") (pintype "unspecified"))
      (node (ref "C30") (pin "2") (pinfunction "2_2") (pintype "unspecified"))
      (node (ref "C33") (pin "2") (pinfunction "2_2") (pintype "unspecified"))
      (node (ref "C34") (pin "1") (pinfunction "1_1") (pintype "unspecified"))
      (node (ref "C35") (pin "1") (pinfunction "1_1") (pintype "input"))
      (node (ref "C36") (pin "1") (pinfunction "1_1") (pintype "input"))
      (node (ref "C37") (pin "1") (pinfunction "1_1") (pintype "input"))
      (node (ref "C38") (pin "2") (pinfunction "2_2") (pintype "input"))
      (node (ref "C39") (pin "2") (pinfunction "2_2") (pintype "input"))
      (node (ref "C4") (pin "1") (pinfunction "1_1") (pintype "unspecified"))
      (node (ref "C40") (pin "1") (pinfunction "1_1") (pintype "unspecified"))
      (node (ref "C41") (pin "2") (pinfunction "2_2") (pintype "unspecified"))
      (node (ref "C44") (pin "1") (pinfunction "1_1") (pintype "input"))
      (node (ref "C45") (pin "1") (pinfunction "1_1") (pintype "input"))
      (node (ref "C46") (pin "2") (pinfunction "2_2") (pintype "unspecified"))
      (node (ref "C49") (pin "2") (pinfunction "2_2") (pintype "input"))
      (node (ref "C5") (pin "1") (pinfunction "1_1") (pintype "unspecified"))
      (node (ref "C50") (pin "1") (pinfunction "1_1") (pintype "unspecified"))
      (node (ref "C51") (pin "2") (pinfunction "2_2") (pintype "input"))
      (node (ref "C52") (pin "1") (pinfunction "1_1") (pintype "unspecified"))
      (node (ref "C53") (pin "1") (pinfunction "1_1") (pintype "unspecified"))
      (node (ref "C54") (pin "1") (pinfunction "1_1") (pintype "unspecified"))
      (node (ref "C55") (pin "1") (pinfunction "1_1") (pintype "input"))
      (node (ref "C57") (pin "1") (pinfunction "1_1") (pintype "unspecified"))
      (node (ref "C58") (pin "1") (pinfunction "1_1") (pintype "input"))
      (node (ref "C59") (pin "1") (pinfunction "1_1") (pintype "unspecified"))
      (node (ref "C6") (pin "1") (pinfunction "1_1") (pintype "unspecified"))
      (node (ref "C60") (pin "1") (pinfunction "1_1") (pintype "input"))
      (node (ref "C61") (pin "1") (pinfunction "1_1") (pintype "unspecified"))
      (node (ref "C62") (pin "1") (pinfunction "1_1") (pintype "unspecified"))
      (node (ref "C63") (pin "1") (pinfunction "1_1") (pintype "input"))
      (node (ref "C7") (pin "1") (pinfunction "1_1") (pintype "unspecified"))
      (node (ref "C8") (pin "1") (pinfunction "1_1") (pintype "unspecified"))
      (node (ref "C9") (pin "1") (pinfunction "1_1") (pintype "unspecified"))
      (node (ref "CN1") (pin "3") (pinfunction "3_3") (pintype "unspecified"))
      (node (ref "CN1") (pin "5") (pinfunction "5_5") (pintype "unspecified"))
      (node (ref "D1") (pin "1") (pinfunction "1_1") (pintype "unspecified"))
      (node (ref "D2") (pin "1") (pinfunction "1_1") (pintype "unspecified"))
      (node (ref "D3") (pin "1") (pinfunction "1_1") (pintype "unspecified"))
      (node (ref "R1") (pin "2") (pinfunction "2_2") (pintype "input"))
      (node (ref "R15") (pin "1") (pinfunction "1_1") (pintype "input"))
      (node (ref "R19") (pin "2") (pinfunction "2_2") (pintype "input"))
      (node (ref "R2") (pin "2") (pinfunction "2_2") (pintype "input"))
      (node (ref "R5") (pin "1") (pinfunction "1_1") (pintype "input"))
      (node (ref "R6") (pin "1") (pinfunction "1_1") (pintype "input"))
      (node (ref "R8") (pin "2") (pinfunction "2_2") (pintype "input"))
      (node (ref "R9") (pin "1") (pinfunction "1_1") (pintype "input"))
      (node (ref "U1") (pin "8") (pinfunction "GND_8") (pintype "unspecified"))
      (node (ref "U1") (pin "9") (pinfunction "GND_9") (pintype "unspecified"))
      (node (ref "U2") (pin "2") (pinfunction "GND_2") (pintype "unspecified"))
      (node (ref "U3") (pin "23") (pinfunction "VSS_23") (pintype "unspecified"))
      (node (ref "U3") (pin "35") (pinfunction "VSS_35") (pintype "unspecified"))
      (node (ref "U3") (pin "47") (pinfunction "VSS_47") (pintype "unspecified"))
      (node (ref "U3") (pin "8") (pinfunction "VSSA/VREF-_8") (pintype "unspecified"))
      (node (ref "U4") (pin "10") (pinfunction "DEMP_10") (pintype "input"))
      (node (ref "U4") (pin "11") (pinfunction "FLT_11") (pintype "input"))
      (node (ref "U4") (pin "16") (pinfunction "FMT_16") (pintype "input"))
      (node (ref "U4") (pin "19") (pinfunction "DGND_19") (pintype "input"))
      (node (ref "U4") (pin "3") (pinfunction "CPGND_3") (pintype "input"))
      (node (ref "U4") (pin "9") (pinfunction "AGND_9") (pintype "input"))
      (node (ref "U5") (pin "10") (pinfunction "GND_10") (pintype "unspecified"))
      (node (ref "U5") (pin "12") (pinfunction "PGND_12") (pintype "unspecified"))
      (node (ref "U5") (pin "20") (pinfunction "PGND_20") (pintype "unspecified"))
      (node (ref "U5") (pin "21") (pinfunction "GAIN_21") (pintype "unspecified"))
      (node (ref "U5") (pin "22") (pinfunction "PGND_22") (pintype "unspecified"))
      (node (ref "U5") (pin "23") (pinfunction "PGND_23") (pintype "unspecified"))
      (node (ref "U5") (pin "31") (pinfunction "PGND_31") (pintype "unspecified"))
      (node (ref "U5") (pin "39") (pinfunction "PGND_39") (pintype "unspecified"))
      (node (ref "U5") (pin "40") (pinfunction "GND_40") (pintype "unspecified"))
      (node (ref "U5") (pin "41") (pinfunction "EP_41") (pintype "unspecified"))
      (node (ref "U5") (pin "9") (pinfunction "GND_9") (pintype "unspecified"))
      (node (ref "U6") (pin "2") (pinfunction "2_2") (pintype "unspecified"))
      (node (ref "USB-C") (pin "1") (pinfunction "EH_1") (pintype "unspecified"))
      (node (ref "USB-C") (pin "2") (pinfunction "EH_2") (pintype "unspecified"))
      (node (ref "USB-C") (pin "3") (pinfunction "EH_3") (pintype "unspecified"))
      (node (ref "USB-C") (pin "4") (pinfunction "EH_4") (pintype "unspecified"))
      (node (ref "USB-C") (pin "A1B12") (pinfunction "GND_A1B12") (pintype "unspecified"))
      (node (ref "USB-C") (pin "B1A12") (pinfunction "GND_B1A12") (pintype "unspecified"))
      (node (ref "X1") (pin "2") (pinfunction "GND_2") (pintype "unspecified"))
    )
    (net (code "11") (name "I2C_SCL") (class "Default")
      (node (ref "U3") (pin "21") (pinfunction "PB10_21") (pintype "unspecified"))
      (node (ref "U6") (pin "6") (pinfunction "6_6") (pintype "unspecified"))
    )
    (net (code "12") (name "I2C_SDA") (class "Default")
      (node (ref "U3") (pin "26") (pinfunction "PB13_26") (pintype "unspecified"))
      (node (ref "U6") (pin "7") (pinfunction "7_7") (pintype "unspecified"))
    )
    (net (code "13") (name "I2S_CK") (class "Default")
      (node (ref "R11") (pin "1") (pinfunction "1_1") (pintype "input"))
      (node (ref "U3") (pin "12") (pinfunction "PA2_12") (pintype "unspecified"))
    )
    (net (code "14") (name "I2S_MCK") (class "Default")
      (node (ref "R10") (pin "1") (pinfunction "1_1") (pintype "input"))
      (node (ref "U3") (pin "15") (pinfunction "PA5_15") (pintype "unspecified"))
    )
    (net (code "15") (name "I2S_SD") (class "Default")
      (node (ref "R12") (pin "1") (pinfunction "1_1") (pintype "input"))
      (node (ref "U3") (pin "14") (pinfunction "PA4_14") (pintype "unspecified"))
    )
    (net (code "16") (name "I2S_WS") (class "Default")
      (node (ref "R13") (pin "1") (pinfunction "1_1") (pintype "input"))
      (node (ref "U3") (pin "11") (pinfunction "PA1_11") (pintype "unspecified"))
    )
    (net (code "17") (name "L_OUT_N") (class "Default")
      (node (ref "C32") (pin "2") (pinfunction "2_2") (pintype "unspecified"))
      (node (ref "L5") (pin "1") (pinfunction "1_1") (pintype "unspecified"))
      (node (ref "U5") (pin "18") (pinfunction "LOUTN_18") (pintype "unspecified"))
      (node (ref "U5") (pin "19") (pinfunction "LFBN_19") (pintype "unspecified"))
    )
    (net (code "18") (name "L_OUT_P") (class "Default")
      (node (ref "C31") (pin "2") (pinfunction "2_2") (pintype "unspecified"))
      (node (ref "L4") (pin "1") (pinfunction "1_1") (pintype "unspecified"))
      (node (ref "U5") (pin "13") (pinfunction "LFBP_13") (pintype "unspecified"))
      (node (ref "U5") (pin "14") (pinfunction "LOUTP_14") (pintype "unspecified"))
    )
    (net (code "19") (name "MUTE") (class "Default")
      (node (ref "R14") (pin "1") (pinfunction "1_1") (pintype "input"))
      (node (ref "U3") (pin "10") (pinfunction "PA0_10") (pintype "unspecified"))
    )
    (net (code "20") (name "Net-(C10-Pad2)") (class "Default")
      (node (ref "C10") (pin "2") (pinfunction "2_2") (pintype "input"))
      (node (ref "U3") (pin "22") (pinfunction "VCAP_22") (pintype "unspecified"))
    )
    (net (code "21") (name "Net-(C12-Pad2)") (class "Default")
      (node (ref "C12") (pin "2") (pinfunction "2_2") (pintype "input"))
      (node (ref "U3") (pin "46") (pinfunction "VCAP_46") (pintype "unspecified"))
    )
    (net (code "22") (name "Net-(C47-Pad1)") (class "Default")
      (node (ref "C47") (pin "1") (pinfunction "1_1") (pintype "input"))
      (node (ref "C48") (pin "2") (pinfunction "2_2") (pintype "unspecified"))
      (node (ref "L1") (pin "1") (pinfunction "1_1") (pintype "unspecified"))
      (node (ref "U5") (pin "24") (pinfunction "SW_24") (pintype "unspecified"))
      (node (ref "U5") (pin "25") (pinfunction "SW_25") (pintype "unspecified"))
    )
    (net (code "23") (name "Net-(C47-Pad2)") (class "Default")
      (node (ref "C47") (pin "2") (pinfunction "2_2") (pintype "input"))
      (node (ref "R22") (pin "2") (pinfunction "2_2") (pintype "input"))
    )
    (net (code "24") (name "Net-(C54-Pad2)") (class "Default")
      (node (ref "C54") (pin "2") (pinfunction "2_2") (pintype "unspecified"))
      (node (ref "C55") (pin "2") (pinfunction "2_2") (pintype "input"))
      (node (ref "C56") (pin "2") (pinfunction "2_2") (pintype "unspecified"))
      (node (ref "CN2") (pin "1") (pinfunction "1_1") (pintype "unspecified"))
      (node (ref "CN2") (pin "2") (pinfunction "2_2") (pintype "unspecified"))
      (node (ref "L2") (pin "2") (pinfunction "2_2") (pintype "unspecified"))
    )
    (net (code "25") (name "Net-(C56-Pad1)") (class "Default")
      (node (ref "C56") (pin "1") (pinfunction "1_1") (pintype "unspecified"))
      (node (ref "C57") (pin "2") (pinfunction "2_2") (pintype "unspecified"))
      (node (ref "C58") (pin "2") (pinfunction "2_2") (pintype "input"))
      (node (ref "CN3") (pin "1") (pinfunction "1_1") (pintype "input"))
      (node (ref "CN3") (pin "2") (pinfunction "2_2") (pintype "input"))
      (node (ref "L3") (pin "2") (pinfunction "2_2") (pintype "unspecified"))
    )
    (net (code "26") (name "Net-(C59-Pad2)") (class "Default")
      (node (ref "C59") (pin "2") (pinfunction "2_2") (pintype "unspecified"))
      (node (ref "C60") (pin "2") (pinfunction "2_2") (pintype "input"))
      (node (ref "C64") (pin "2") (pinfunction "2_2") (pintype "unspecified"))
      (node (ref "CN4") (pin "1") (pinfunction "1_1") (pintype "unspecified"))
      (node (ref "CN4") (pin "2") (pinfunction "2_2") (pintype "unspecified"))
      (node (ref "L4") (pin "2") (pinfunction "2_2") (pintype "unspecified"))
    )
    (net (code "27") (name "Net-(C62-Pad2)") (class "Default")
      (node (ref "C62") (pin "2") (pinfunction "2_2") (pintype "unspecified"))
      (node (ref "C63") (pin "2") (pinfunction "2_2") (pintype "input"))
      (node (ref "C64") (pin "1") (pinfunction "1_1") (pintype "unspecified"))
      (node (ref "CN5") (pin "1") (pinfunction "1_1") (pintype "input"))
      (node (ref "CN5") (pin "2") (pinfunction "2_2") (pintype "input"))
      (node (ref "L5") (pin "2") (pinfunction "2_2") (pintype "unspecified"))
    )
    (net (code "28") (name "Net-(CN1-Pad9)") (class "Default")
      (node (ref "CN1") (pin "9") (pinfunction "9_9") (pintype "unspecified"))
      (node (ref "R9") (pin "2") (pinfunction "2_2") (pintype "input"))
    )
    (net (code "29") (name "Net-(LED1-A)") (class "Default")
      (node (ref "LED1") (pin "2") (pinfunction "A_2") (pintype "input"))
      (node (ref "R3") (pin "1") (pinfunction "1_1") (pintype "input"))
    )
    (net (code "30") (name "Net-(LED1-K)") (class "Default")
      (node (ref "LED1") (pin "1") (pinfunction "K_1") (pintype "input"))
      (node (ref "U1") (pin "6") (pinfunction "FLT#_6") (pintype "unspecified"))
    )
    (net (code "31") (name "Net-(LED2-A)") (class "Default")
      (node (ref "LED2") (pin "2") (pinfunction "A_2") (pintype "input"))
      (node (ref "R18") (pin "1") (pinfunction "1_1") (pintype "input"))
    )
    (net (code "32") (name "Net-(LED2-K)") (class "Default")
      (node (ref "LED2") (pin "1") (pinfunction "K_1") (pintype "input"))
      (node (ref "U5") (pin "1") (pinfunction "FLT_1") (pintype "unspecified"))
    )
    (net (code "33") (name "Net-(U1-EN{slash}UVLO)") (class "Default")
      (node (ref "R4") (pin "1") (pinfunction "1_1") (pintype "input"))
      (node (ref "R5") (pin "2") (pinfunction "2_2") (pintype "input"))
      (node (ref "U1") (pin "2") (pinfunction "EN/UVLO_2") (pintype "unspecified"))
    )
    (net (code "34") (name "Net-(U1-ILM)") (class "Default")
      (node (ref "R6") (pin "2") (pinfunction "2_2") (pintype "input"))
      (node (ref "U1") (pin "7") (pinfunction "ILM_7") (pintype "unspecified"))
    )
    (net (code "35") (name "Net-(U1-dVdt)") (class "Default")
      (node (ref "C1") (pin "1") (pinfunction "1_1") (pintype "input"))
      (node (ref "U1") (pin "1") (pinfunction "dVdt_1") (pintype "unspecified"))
    )
    (net (code "36") (name "Net-(U3-BOOT0)") (class "Default")
      (node (ref "R8") (pin "1") (pinfunction "1_1") (pintype "input"))
      (node (ref "SW1") (pin "1") (pinfunction "1_1") (pintype "unspecified"))
      (node (ref "U3") (pin "44") (pinfunction "BOOT0_44") (pintype "unspecified"))
    )
    (net (code "37") (name "Net-(U3-PA7)") (class "Default")
      (node (ref "R7") (pin "2") (pinfunction "2_2") (pintype "input"))
      (node (ref "U3") (pin "17") (pinfunction "PA7_17") (pintype "unspecified"))
    )
    (net (code "38") (name "Net-(U4-BCK)") (class "Default")
      (node (ref "R11") (pin "2") (pinfunction "2_2") (pintype "input"))
      (node (ref "U4") (pin "13") (pinfunction "BCK_13") (pintype "input"))
    )
    (net (code "39") (name "Net-(U4-CAPM)") (class "Default")
      (node (ref "C24") (pin "2") (pinfunction "2_2") (pintype "input"))
      (node (ref "U4") (pin "4") (pinfunction "CAPM_4") (pintype "input"))
    )
    (net (code "40") (name "Net-(U4-CAPP)") (class "Default")
      (node (ref "C24") (pin "1") (pinfunction "1_1") (pintype "input"))
      (node (ref "U4") (pin "2") (pinfunction "CAPP_2") (pintype "input"))
    )
    (net (code "41") (name "Net-(U4-DIN)") (class "Default")
      (node (ref "R12") (pin "2") (pinfunction "2_2") (pintype "input"))
      (node (ref "U4") (pin "14") (pinfunction "DIN_14") (pintype "input"))
    )
    (net (code "42") (name "Net-(U4-LDOO)") (class "Default")
      (node (ref "C15") (pin "2") (pinfunction "2_2") (pintype "unspecified"))
      (node (ref "C16") (pin "2") (pinfunction "2_2") (pintype "unspecified"))
      (node (ref "U4") (pin "18") (pinfunction "LDOO_18") (pintype "input"))
    )
    (net (code "43") (name "Net-(U4-LRCK)") (class "Default")
      (node (ref "R13") (pin "2") (pinfunction "2_2") (pintype "input"))
      (node (ref "U4") (pin "15") (pinfunction "LRCK_15") (pintype "input"))
    )
    (net (code "44") (name "Net-(U4-OUTL)") (class "Default")
      (node (ref "R17") (pin "1") (pinfunction "1_1") (pintype "input"))
      (node (ref "U4") (pin "6") (pinfunction "OUTL_6") (pintype "input"))
    )
    (net (code "45") (name "Net-(U4-OUTR)") (class "Default")
      (node (ref "R16") (pin "1") (pinfunction "1_1") (pintype "input"))
      (node (ref "U4") (pin "7") (pinfunction "OUTR_7") (pintype "input"))
    )
    (net (code "46") (name "Net-(U4-SCK)") (class "Default")
      (node (ref "R10") (pin "2") (pinfunction "2_2") (pintype "input"))
      (node (ref "U4") (pin "12") (pinfunction "SCK_12") (pintype "input"))
    )
    (net (code "47") (name "Net-(U4-VNEG)") (class "Default")
      (node (ref "C23") (pin "2") (pinfunction "2_2") (pintype "input"))
      (node (ref "U4") (pin "5") (pinfunction "VNEG_5") (pintype "input"))
    )
    (net (code "48") (name "Net-(U4-XSMT)") (class "Default")
      (node (ref "R14") (pin "2") (pinfunction "2_2") (pintype "input"))
      (node (ref "R15") (pin "2") (pinfunction "2_2") (pintype "input"))
      (node (ref "U4") (pin "17") (pinfunction "XSMT_17") (pintype "input"))
    )
    (net (code "49") (name "Net-(U5-BST)") (class "Default")
      (node (ref "C48") (pin "1") (pinfunction "1_1") (pintype "unspecified"))
      (node (ref "U5") (pin "26") (pinfunction "BST_26") (pintype "unspecified"))
    )
    (net (code "50") (name "Net-(U5-EN)") (class "Default")
      (node (ref "R19") (pin "1") (pinfunction "1_1") (pintype "input"))
      (node (ref "R20") (pin "2") (pinfunction "2_2") (pintype "input"))
      (node (ref "U5") (pin "2") (pinfunction "EN_2") (pintype "unspecified"))
    )
    (net (code "51") (name "Net-(U5-LBSTN)") (class "Default")
      (node (ref "C32") (pin "1") (pinfunction "1_1") (pintype "unspecified"))
      (node (ref "U5") (pin "17") (pinfunction "LBSTN_17") (pintype "unspecified"))
    )
    (net (code "52") (name "Net-(U5-LBSTP)") (class "Default")
      (node (ref "C31") (pin "1") (pinfunction "1_1") (pintype "unspecified"))
      (node (ref "U5") (pin "15") (pinfunction "LBSTP_15") (pintype "unspecified"))
    )
    (net (code "53") (name "Net-(U5-LINN)") (class "Default")
      (node (ref "C29") (pin "1") (pinfunction "1_1") (pintype "unspecified"))
      (node (ref "U5") (pin "5") (pinfunction "LINN_5") (pintype "unspecified"))
    )
    (net (code "54") (name "Net-(U5-LINP)") (class "Default")
      (node (ref "C30") (pin "1") (pinfunction "1_1") (pintype "unspecified"))
      (node (ref "U5") (pin "6") (pinfunction "LINP_6") (pintype "unspecified"))
    )
    (net (code "55") (name "Net-(U5-RBSTN)") (class "Default")
      (node (ref "C43") (pin "2") (pinfunction "2_2") (pintype "unspecified"))
      (node (ref "U5") (pin "34") (pinfunction "RBSTN_34") (pintype "unspecified"))
    )
    (net (code "56") (name "Net-(U5-RBSTP)") (class "Default")
      (node (ref "C42") (pin "1") (pinfunction "1_1") (pintype "unspecified"))
      (node (ref "U5") (pin "36") (pinfunction "RBSTP_36") (pintype "unspecified"))
    )
    (net (code "57") (name "Net-(U5-RINN)") (class "Default")
      (node (ref "C28") (pin "1") (pinfunction "1_1") (pintype "unspecified"))
      (node (ref "U5") (pin "4") (pinfunction "RINN_4") (pintype "unspecified"))
    )
    (net (code "58") (name "Net-(U5-RINP)") (class "Default")
      (node (ref "C27") (pin "1") (pinfunction "1_1") (pintype "unspecified"))
      (node (ref "U5") (pin "3") (pinfunction "RINP_3") (pintype "unspecified"))
    )
    (net (code "59") (name "Net-(U5-SSM)") (class "Default")
      (node (ref "R21") (pin "2") (pinfunction "2_2") (pintype "input"))
      (node (ref "U5") (pin "7") (pinfunction "SSM_7") (pintype "unspecified"))
    )
    (net (code "60") (name "Net-(X1-OUT)") (class "Default")
      (node (ref "R7") (pin "1") (pinfunction "1_1") (pintype "input"))
      (node (ref "X1") (pin "3") (pinfunction "OUT_3") (pintype "unspecified"))
    )
    (net (code "61") (name "PLIM") (class "Default")
      (node (ref "R23") (pin "2") (pinfunction "2_2") (pintype "input"))
      (node (ref "U5") (pin "11") (pinfunction "PLIM_11") (pintype "unspecified"))
    )
    (net (code "62") (name "PUSH") (class "Default")
      (node (ref "U3") (pin "29") (pinfunction "PA8_29") (pintype "unspecified"))
      (node (ref "U6") (pin "5") (pinfunction "5_5") (pintype "unspecified"))
    )
    (net (code "63") (name "PVDD") (class "Default")
      (node (ref "C33") (pin "1") (pinfunction "1_1") (pintype "unspecified"))
      (node (ref "C34") (pin "2") (pinfunction "2_2") (pintype "unspecified"))
      (node (ref "C35") (pin "2") (pinfunction "2_2") (pintype "input"))
      (node (ref "C36") (pin "2") (pinfunction "2_2") (pintype "input"))
      (node (ref "C37") (pin "2") (pinfunction "2_2") (pintype "input"))
      (node (ref "C38") (pin "1") (pinfunction "1_1") (pintype "input"))
      (node (ref "C39") (pin "1") (pinfunction "1_1") (pintype "input"))
      (node (ref "C40") (pin "2") (pinfunction "2_2") (pintype "unspecified"))
      (node (ref "C41") (pin "1") (pinfunction "1_1") (pintype "unspecified"))
      (node (ref "U5") (pin "16") (pinfunction "LPVDD_16") (pintype "unspecified"))
      (node (ref "U5") (pin "27") (pinfunction "PVDD_27") (pintype "unspecified"))
      (node (ref "U5") (pin "28") (pinfunction "PVDD_28") (pintype "unspecified"))
      (node (ref "U5") (pin "35") (pinfunction "RPVDD_35") (pintype "unspecified"))
    )
    (net (code "64") (name "RST") (class "Default")
      (node (ref "CN1") (pin "10") (pinfunction "10_10") (pintype "unspecified"))
      (node (ref "U3") (pin "7") (pinfunction "NRST_7") (pintype "unspecified"))
    )
    (net (code "65") (name "R_OUT_N") (class "Default")
      (node (ref "C43") (pin "1") (pinfunction "1_1") (pintype "unspecified"))
      (node (ref "L3") (pin "1") (pinfunction "1_1") (pintype "unspecified"))
      (node (ref "U5") (pin "32") (pinfunction "RFBN_32") (pintype "unspecified"))
      (node (ref "U5") (pin "33") (pinfunction "ROUTN_33") (pintype "unspecified"))
    )
    (net (code "66") (name "R_OUT_P") (class "Default")
      (node (ref "C42") (pin "2") (pinfunction "2_2") (pintype "unspecified"))
      (node (ref "L2") (pin "1") (pinfunction "1_1") (pintype "unspecified"))
      (node (ref "U5") (pin "37") (pinfunction "ROUTP_37") (pintype "unspecified"))
      (node (ref "U5") (pin "38") (pinfunction "RFBP_38") (pintype "unspecified"))
    )
    (net (code "67") (name "SWCLK") (class "Default")
      (node (ref "CN1") (pin "4") (pinfunction "4_4") (pintype "unspecified"))
      (node (ref "U3") (pin "37") (pinfunction "PA14_37") (pintype "unspecified"))
    )
    (net (code "68") (name "SWDIO") (class "Default")
      (node (ref "CN1") (pin "2") (pinfunction "2_2") (pintype "unspecified"))
      (node (ref "U3") (pin "34") (pinfunction "PA13_34") (pintype "unspecified"))
    )
    (net (code "69") (name "TRIM_A") (class "Default")
      (node (ref "U3") (pin "28") (pinfunction "PB15_28") (pintype "unspecified"))
      (node (ref "U6") (pin "4") (pinfunction "4_4") (pintype "unspecified"))
    )
    (net (code "70") (name "TRIM_B") (class "Default")
      (node (ref "U3") (pin "27") (pinfunction "PB14_27") (pintype "unspecified"))
      (node (ref "U6") (pin "3") (pinfunction "3_3") (pintype "unspecified"))
    )
    (net (code "71") (name "VBUS") (class "Default")
      (node (ref "C2") (pin "2") (pinfunction "2_2") (pintype "unspecified"))
      (node (ref "D1") (pin "2") (pinfunction "2_2") (pintype "unspecified"))
      (node (ref "R3") (pin "2") (pinfunction "2_2") (pintype "input"))
      (node (ref "R4") (pin "2") (pinfunction "2_2") (pintype "input"))
      (node (ref "U1") (pin "3") (pinfunction "IN_3") (pintype "unspecified"))
      (node (ref "U1") (pin "4") (pinfunction "IN_4") (pintype "unspecified"))
      (node (ref "USB-C") (pin "A4B9") (pinfunction "VBUS_A4B9") (pintype "unspecified"))
      (node (ref "USB-C") (pin "B4A9") (pinfunction "VBUS_B4A9") (pintype "unspecified"))
    )
    (net (code "72") (name "VDD") (class "Default")
      (node (ref "C52") (pin "2") (pinfunction "2_2") (pintype "unspecified"))
      (node (ref "C53") (pin "2") (pinfunction "2_2") (pintype "unspecified"))
      (node (ref "R23") (pin "1") (pinfunction "1_1") (pintype "input"))
      (node (ref "U5") (pin "8") (pinfunction "VDD_8") (pintype "unspecified"))
    )
    (net (code "73") (name "unconnected-(CN1-Pad6)") (class "Default")
      (node (ref "CN1") (pin "6") (pinfunction "6_6") (pintype "unspecified"))
    )
    (net (code "74") (name "unconnected-(CN1-Pad7)") (class "Default")
      (node (ref "CN1") (pin "7") (pinfunction "7_7") (pintype "unspecified"))
    )
    (net (code "75") (name "unconnected-(CN1-Pad8)") (class "Default")
      (node (ref "CN1") (pin "8") (pinfunction "8_8") (pintype "unspecified"))
    )
    (net (code "76") (name "unconnected-(U2-NC-Pad4)") (class "Default")
      (node (ref "U2") (pin "4") (pinfunction "NC_4") (pintype "unspecified"))
    )
    (net (code "77") (name "unconnected-(U3-PA3-Pad13)") (class "Default")
      (node (ref "U3") (pin "13") (pinfunction "PA3_13") (pintype "unspecified"))
    )
    (net (code "78") (name "unconnected-(U3-PA6-Pad16)") (class "Default")
      (node (ref "U3") (pin "16") (pinfunction "PA6_16") (pintype "unspecified"))
    )
    (net (code "79") (name "unconnected-(U3-PA9-Pad30)") (class "Default")
      (node (ref "U3") (pin "30") (pinfunction "PA9_30") (pintype "unspecified"))
    )
    (net (code "80") (name "unconnected-(U3-PA10-Pad31)") (class "Default")
      (node (ref "U3") (pin "31") (pinfunction "PA10_31") (pintype "unspecified"))
    )
    (net (code "81") (name "unconnected-(U3-PA15-Pad38)") (class "Default")
      (node (ref "U3") (pin "38") (pinfunction "PA15_38") (pintype "unspecified"))
    )
    (net (code "82") (name "unconnected-(U3-PB2-Pad20)") (class "Default")
      (node (ref "U3") (pin "20") (pinfunction "PB2_20") (pintype "unspecified"))
    )
    (net (code "83") (name "unconnected-(U3-PB3-Pad39)") (class "Default")
      (node (ref "U3") (pin "39") (pinfunction "PB3_39") (pintype "unspecified"))
    )
    (net (code "84") (name "unconnected-(U3-PB4-Pad40)") (class "Default")
      (node (ref "U3") (pin "40") (pinfunction "PB4_40") (pintype "unspecified"))
    )
    (net (code "85") (name "unconnected-(U3-PB5-Pad41)") (class "Default")
      (node (ref "U3") (pin "41") (pinfunction "PB5_41") (pintype "unspecified"))
    )
    (net (code "86") (name "unconnected-(U3-PB6-Pad42)") (class "Default")
      (node (ref "U3") (pin "42") (pinfunction "PB6_42") (pintype "unspecified"))
    )
    (net (code "87") (name "unconnected-(U3-PB7-Pad43)") (class "Default")
      (node (ref "U3") (pin "43") (pinfunction "PB7_43") (pintype "unspecified"))
    )
    (net (code "88") (name "unconnected-(U3-PB8-Pad45)") (class "Default")
      (node (ref "U3") (pin "45") (pinfunction "PB8_45") (pintype "unspecified"))
    )
    (net (code "89") (name "unconnected-(U3-PC13-Pad2)") (class "Default")
      (node (ref "U3") (pin "2") (pinfunction "PC13_2") (pintype "unspecified"))
    )
    (net (code "90") (name "unconnected-(U3-PC14-OSC32_IN-Pad3)") (class "Default")
      (node (ref "U3") (pin "3") (pinfunction "PC14-OSC32_IN_3") (pintype "unspecified"))
    )
    (net (code "91") (name "unconnected-(U3-PC15-OSC32_OUT-Pad4)") (class "Default")
      (node (ref "U3") (pin "4") (pinfunction "PC15-OSC32_OUT_4") (pintype "unspecified"))
    )
    (net (code "92") (name "unconnected-(U3-PH0-OSC_IN-Pad5)") (class "Default")
      (node (ref "U3") (pin "5") (pinfunction "PH0-OSC_IN_5") (pintype "unspecified"))
    )
    (net (code "93") (name "unconnected-(U3-PH1-OSC_OUT-Pad6)") (class "Default")
      (node (ref "U3") (pin "6") (pinfunction "PH1-OSC_OUT_6") (pintype "unspecified"))
    )
    (net (code "94") (name "unconnected-(USB-C-SBU1-PadA8)") (class "Default")
      (node (ref "USB-C") (pin "A8") (pinfunction "SBU1_A8") (pintype "unspecified"))
    )
    (net (code "95") (name "unconnected-(USB-C-SBU2-PadB8)") (class "Default")
      (node (ref "USB-C") (pin "B8") (pinfunction "SBU2_B8") (pintype "unspecified"))
    )
  )
)
